# Control_HAT_v0_1B.net
KiCad netlist of a schematic drawn in EAGLE
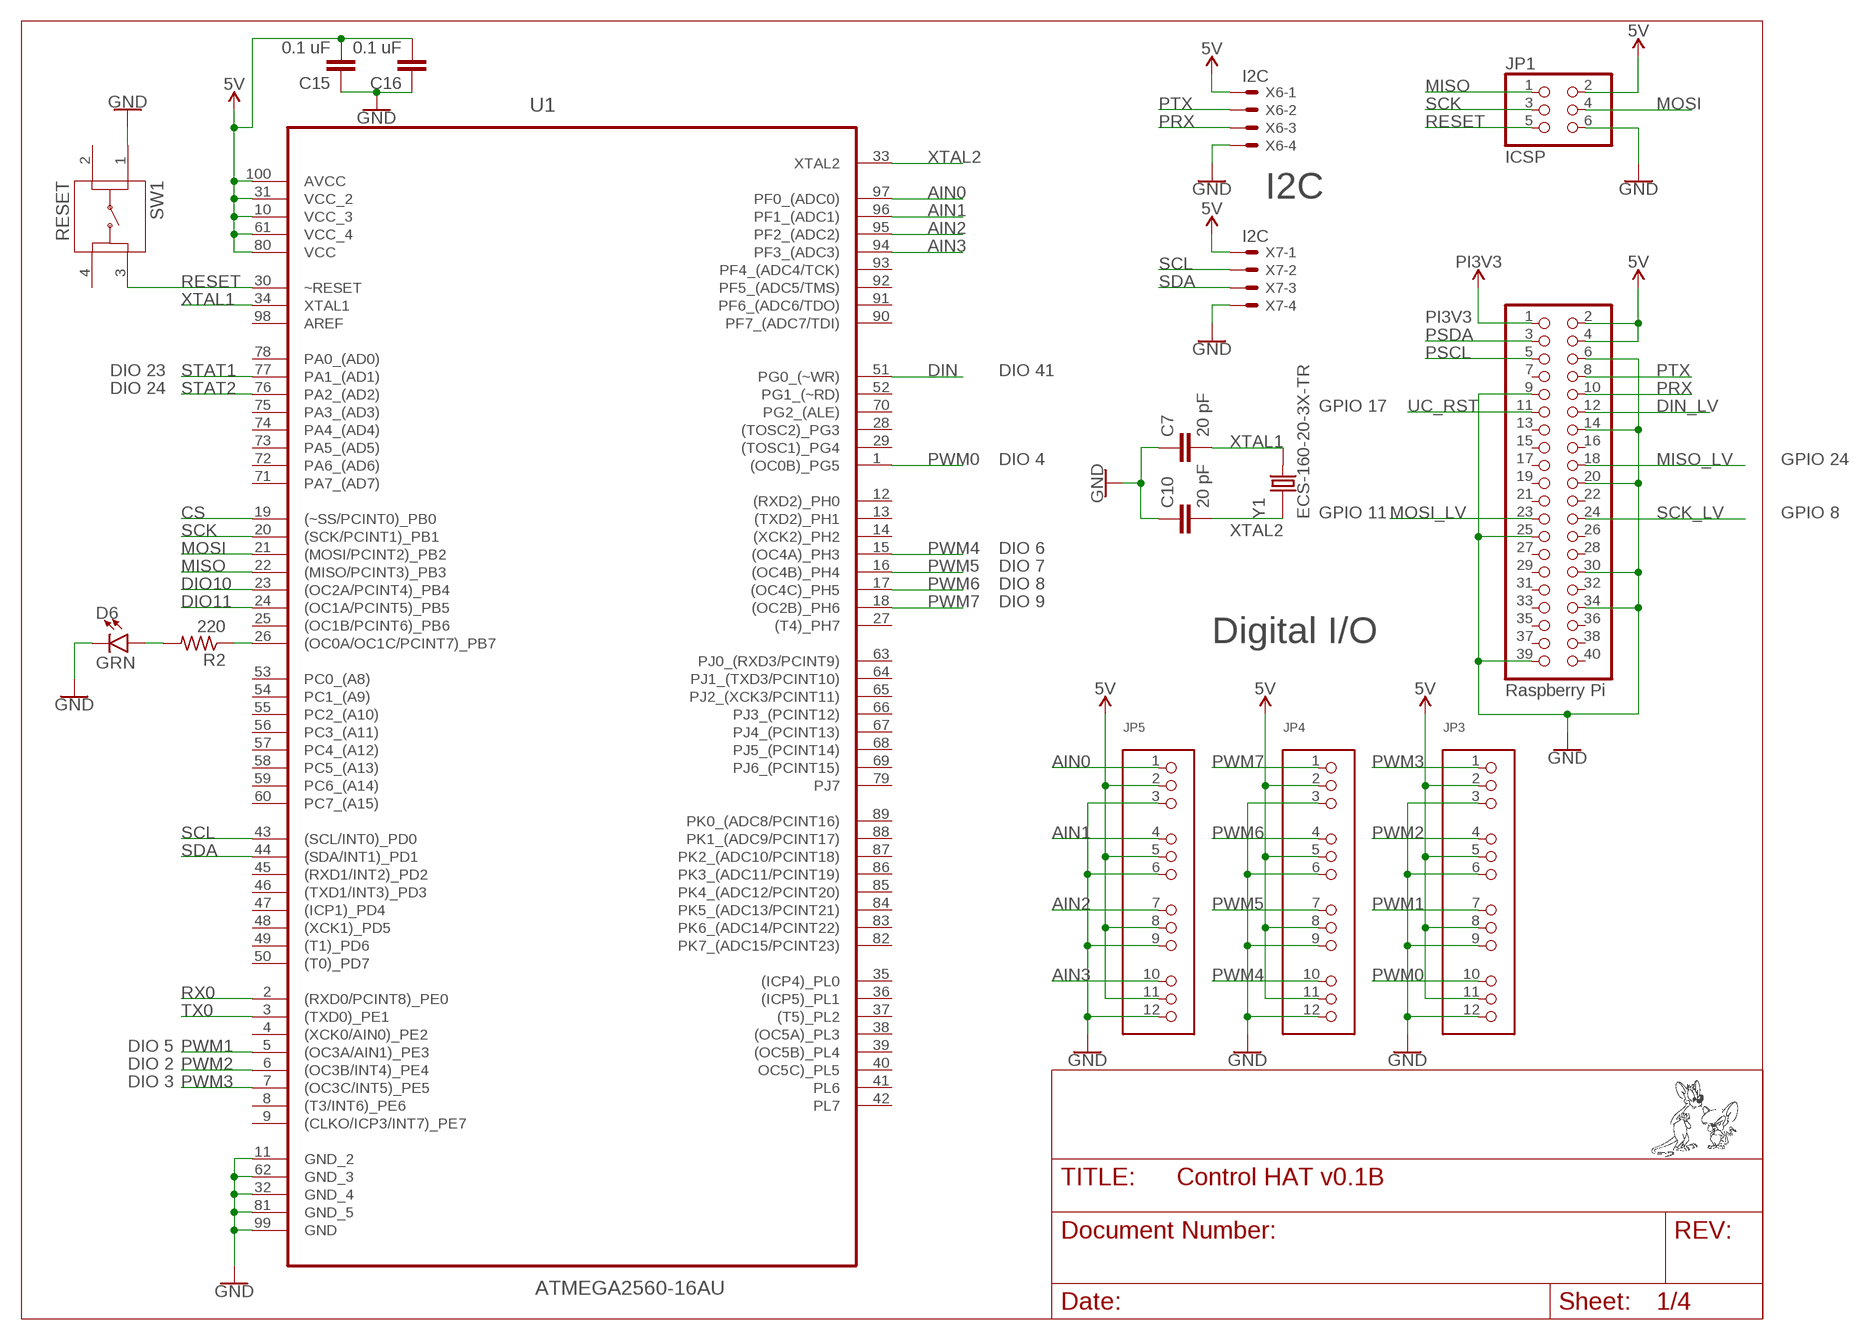
[diagram p0: schematic, sheet 1]
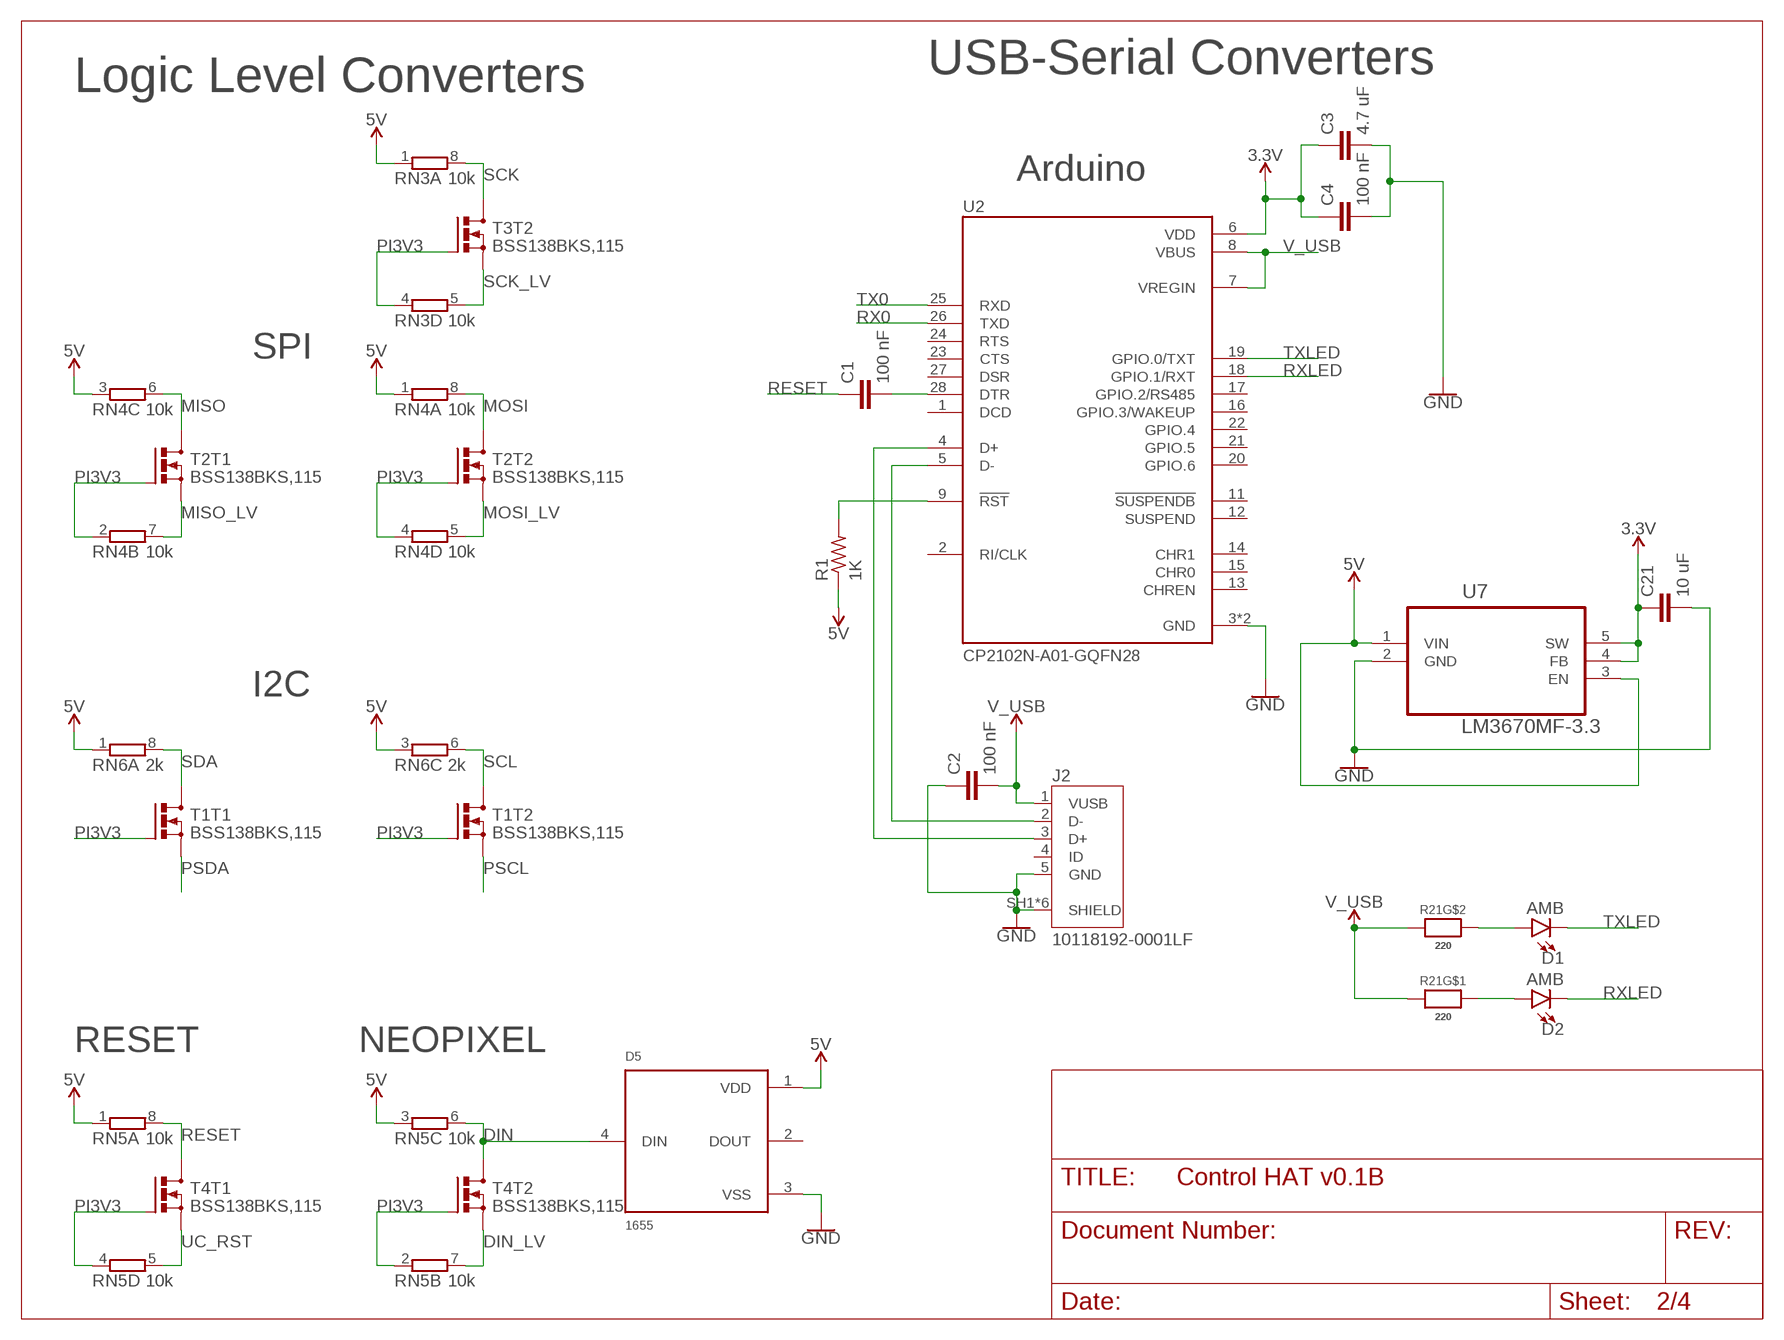
[diagram p1: schematic, sheet 2]
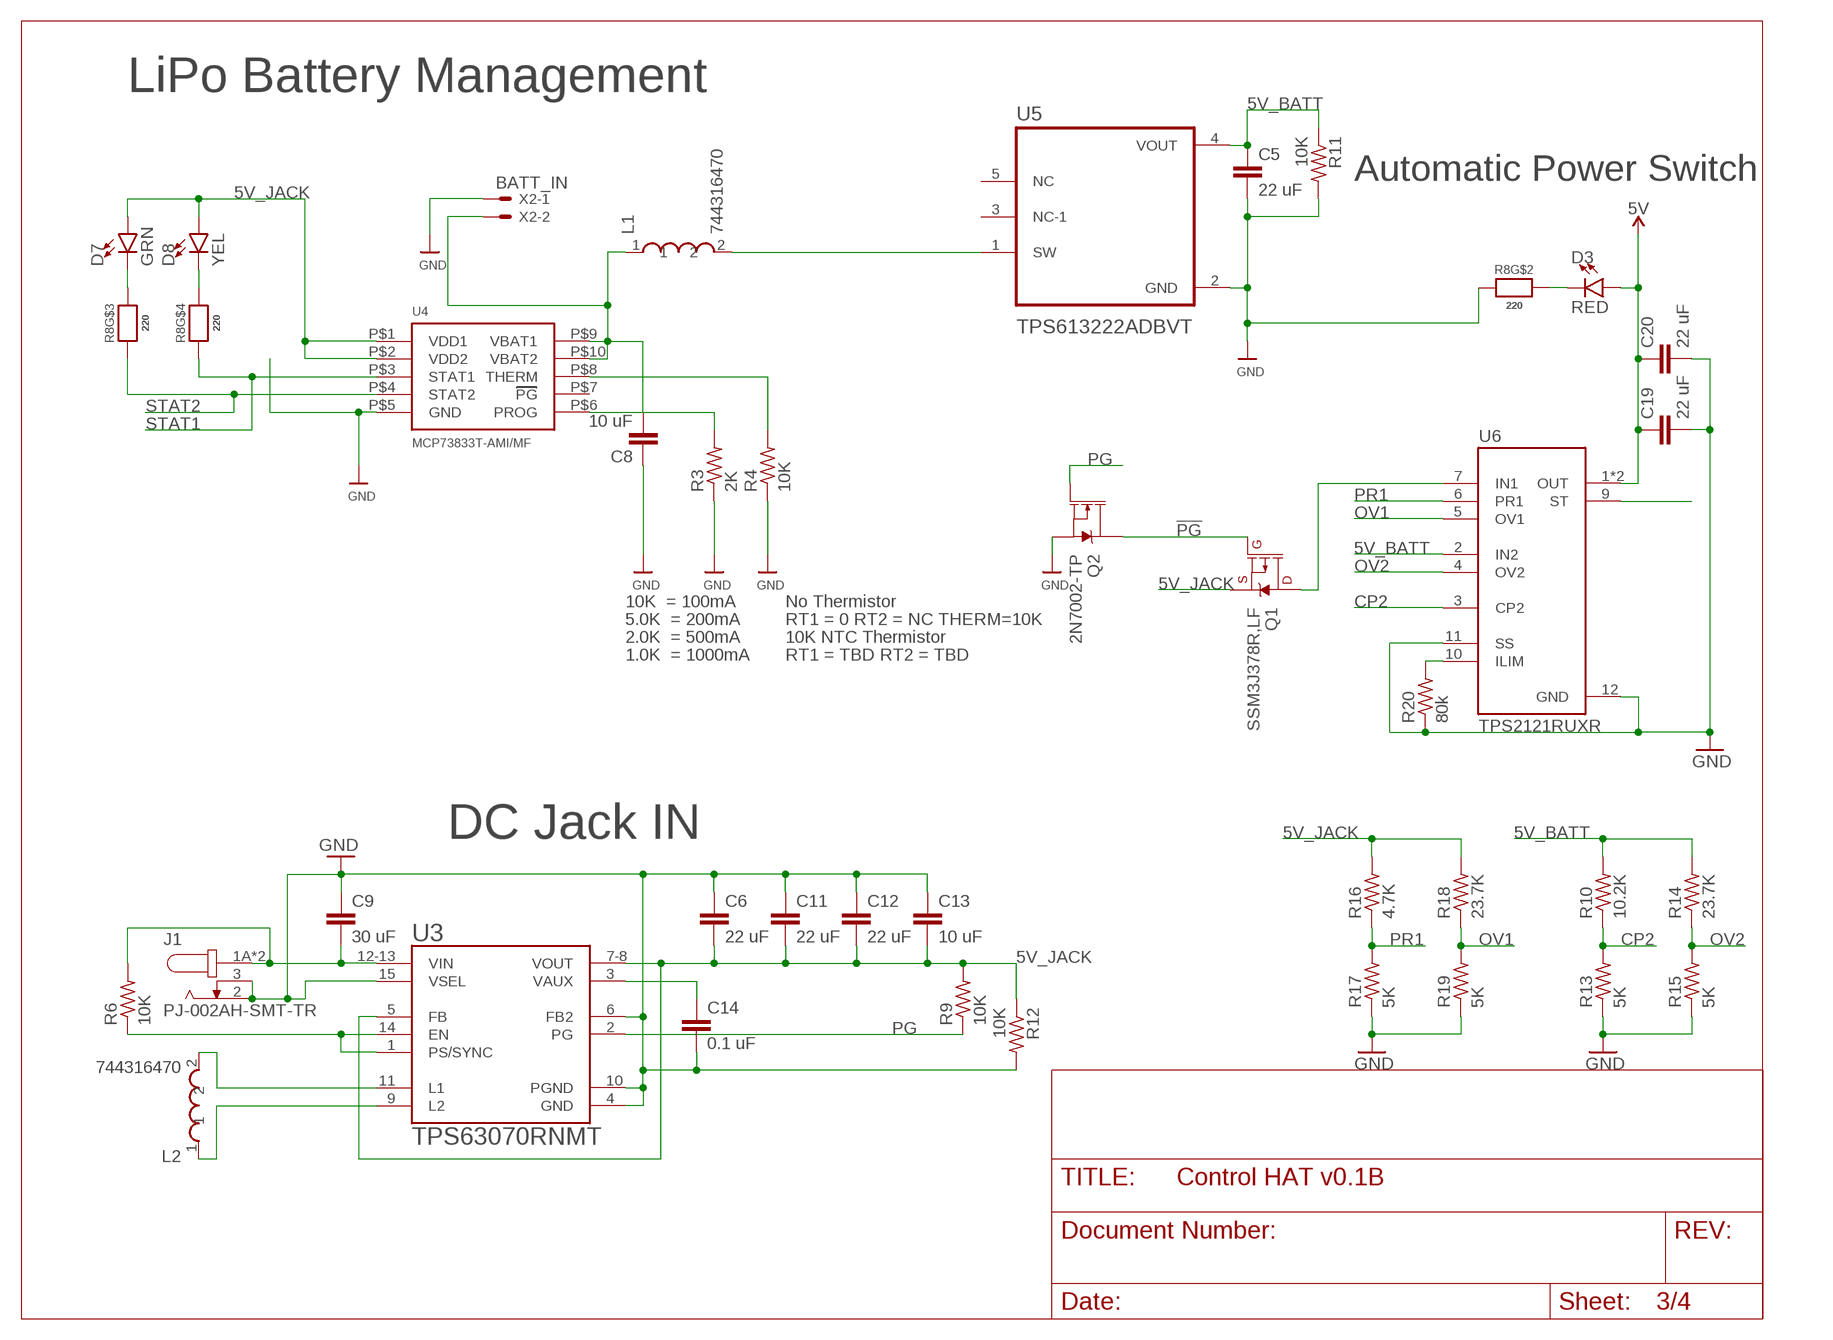
[diagram p2: schematic, sheet 3]
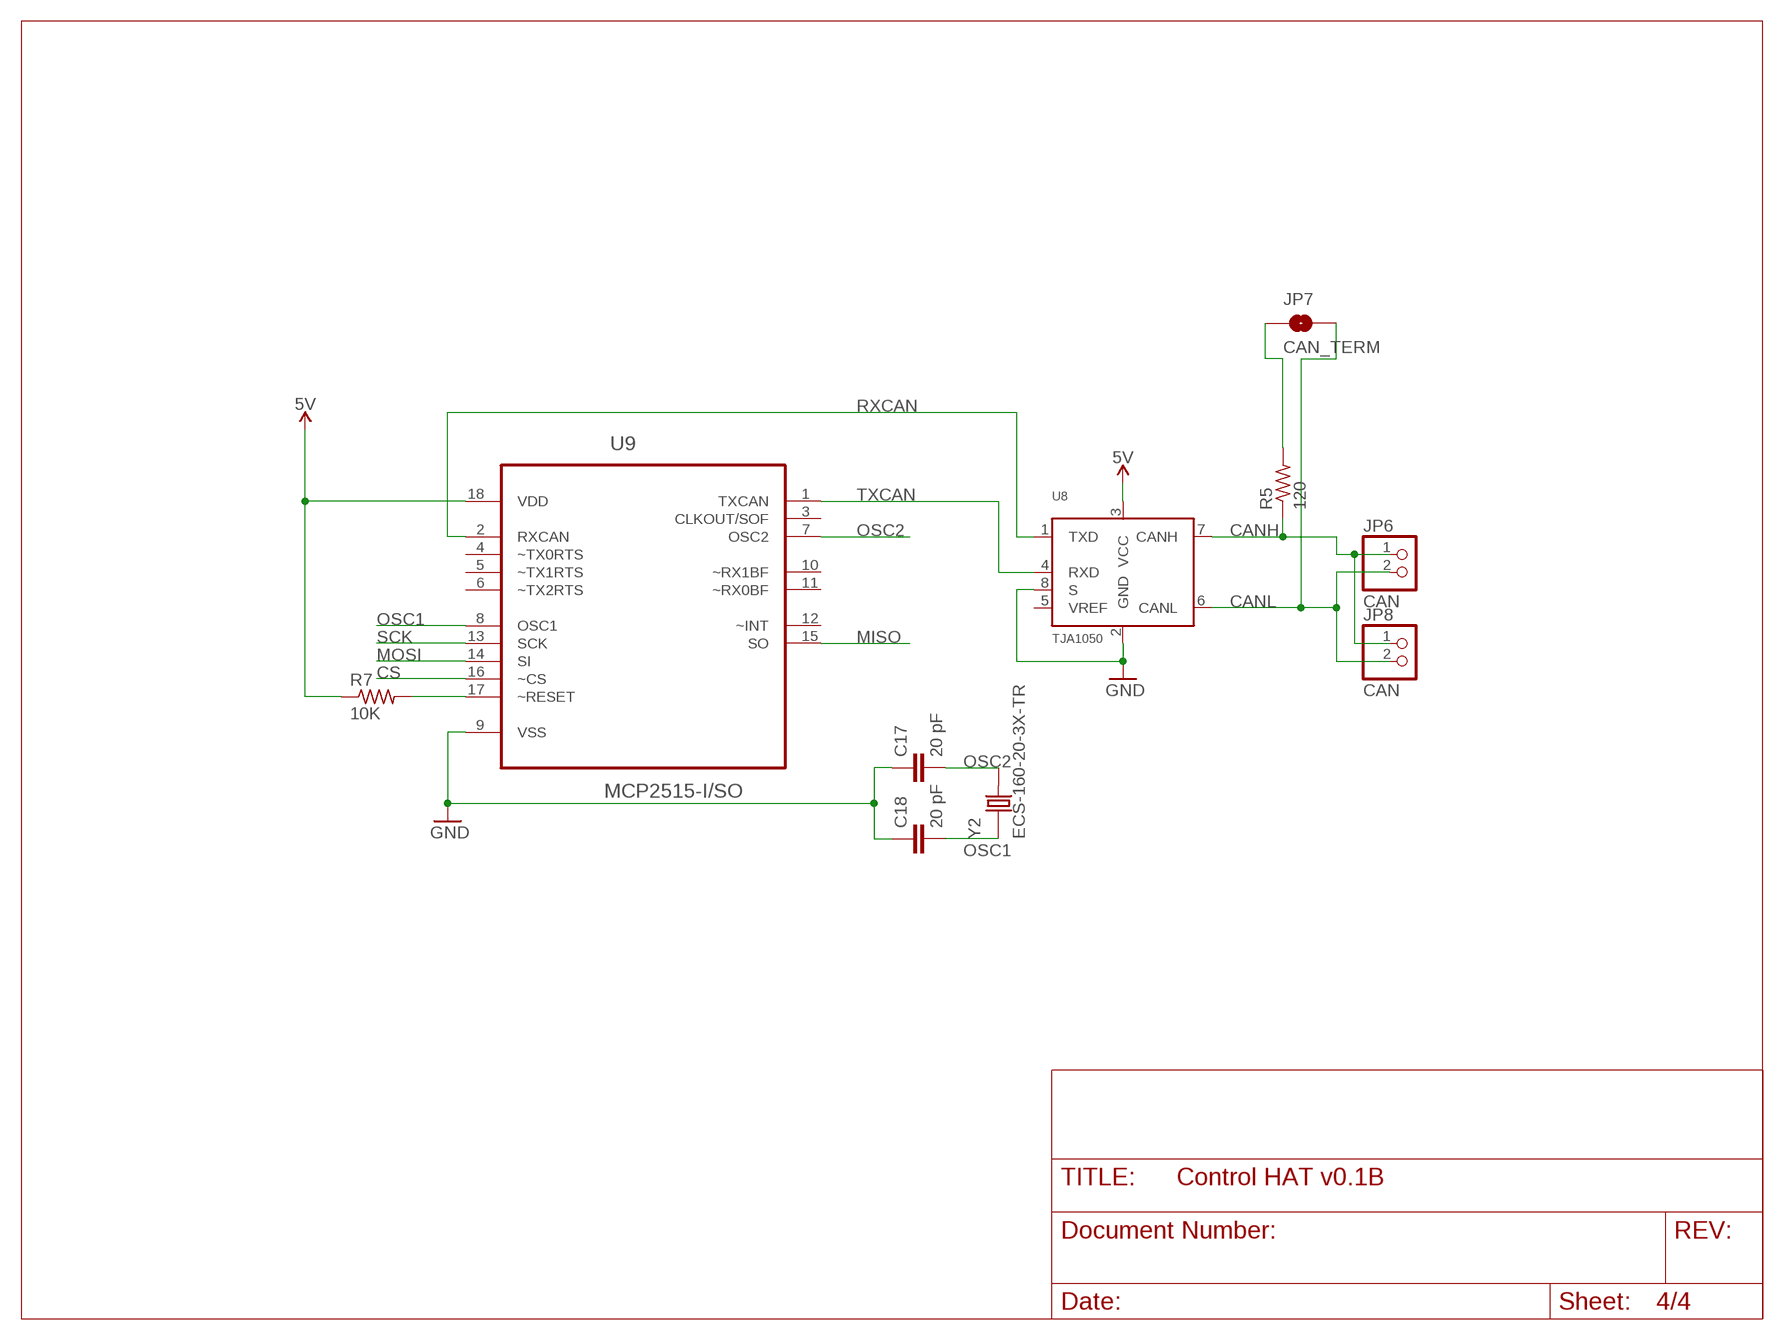
[diagram p3: schematic, sheet 4]

(export (version "E")
  (design (tool "Eeschema 10.0.6"))
  (components
    (comp (ref "C1")
      (value "100 nF")
      (footprint "eagle-import:C0603")
      (libsource (lib "eagle-import") (part "C-EUC0603"))
    )
    (comp (ref "C2")
      (value "100 nF")
      (footprint "eagle-import:C0603")
      (libsource (lib "eagle-import") (part "C-EUC0603"))
    )
    (comp (ref "C3")
      (value "4.7 uF")
      (footprint "eagle-import:C0603")
      (libsource (lib "eagle-import") (part "C-EUC0603"))
    )
    (comp (ref "C4")
      (value "100 nF")
      (footprint "eagle-import:C0603")
      (libsource (lib "eagle-import") (part "C-EUC0603"))
    )
    (comp (ref "C21")
      (value "10 uF")
      (footprint "eagle-import:C0603")
      (libsource (lib "eagle-import") (part "C-EUC0603"))
    )
    (comp (ref "D1")
      (value "AMB")
      (footprint "eagle-import:LED-0603")
      (libsource (lib "eagle-import") (part "LED0603"))
    )
    (comp (ref "D2")
      (value "AMB")
      (footprint "eagle-import:LED-0603")
      (libsource (lib "eagle-import") (part "LED0603"))
    )
    (comp (ref "D5")
      (value "1655")
      (footprint "eagle-import:FCI_1655")
      (fields (field (name "MF") "Adafruit Industries"))
      (libsource (lib "eagle-import") (part "1655"))
    )
    (comp (ref "J2")
      (value "10118192-0001LF")
      (footprint "eagle-import:AMPHENOL_10118192-0001LF")
      (fields (field (name "MF") "Amphenol ICC"))
      (libsource (lib "eagle-import") (part "10118192-0001LF"))
    )
    (comp (ref "R1")
      (value "1K")
      (footprint "eagle-import:R0603")
      (libsource (lib "eagle-import") (part "R-US_R0603"))
    )
    (comp (ref "R21")
      (value "220")
      (footprint "eagle-import:RESPACK_4X0603")
      (libsource (lib "eagle-import") (part "RESISTOR_4PACK"))
    )
    (comp (ref "RN3")
      (value "10k")
      (footprint "eagle-import:EXB28V")
      (libsource (lib "eagle-import") (part "4R-NEXB28V"))
    )
    (comp (ref "RN4")
      (value "10k")
      (footprint "eagle-import:EXB28V")
      (libsource (lib "eagle-import") (part "4R-NEXB28V"))
    )
    (comp (ref "RN5")
      (value "10k")
      (footprint "eagle-import:EXB28V")
      (libsource (lib "eagle-import") (part "4R-NEXB28V"))
    )
    (comp (ref "RN6")
      (value "2k")
      (footprint "eagle-import:EXB28V")
      (libsource (lib "eagle-import") (part "4R-NEXB28V"))
    )
    (comp (ref "T1")
      (value "BSS138BKS,115")
      (footprint "eagle-import:SOT363")
      (fields (field (name "MF") "Nexperia USA"))
      (libsource (lib "eagle-import") (part "BSS138BKS,115"))
    )
    (comp (ref "T2")
      (value "BSS138BKS,115")
      (footprint "eagle-import:SOT363")
      (fields (field (name "MF") "Nexperia USA"))
      (libsource (lib "eagle-import") (part "BSS138BKS,115"))
    )
    (comp (ref "T3")
      (value "BSS138BKS,115")
      (footprint "eagle-import:SOT363")
      (fields (field (name "MF") "Nexperia USA"))
      (libsource (lib "eagle-import") (part "BSS138BKS,115"))
    )
    (comp (ref "T4")
      (value "BSS138BKS,115")
      (footprint "eagle-import:SOT363")
      (fields (field (name "MF") "Nexperia USA"))
      (libsource (lib "eagle-import") (part "BSS138BKS,115"))
    )
    (comp (ref "U2")
      (value "CP2102N-A01-GQFN28")
      (footprint "eagle-import:QFN50P500X500X80-29N")
      (fields (field (name "MF") "Silicon Labs"))
      (libsource (lib "eagle-import") (part "CP2102N-A01-GQFN28"))
    )
    (comp (ref "U7")
      (value "LM3670MF-3.3")
      (footprint "eagle-import:SOT95P284X122-5N")
      (fields (field (name "MF") "Texas Instruments") (field (name "MP") "LM3670MF-3.3/NOPB"))
      (libsource (lib "eagle-import") (part "LM3670MF-3.3"))
    )
    (comp (ref "C17")
      (value "20 pF")
      (footprint "eagle-import:C0603")
      (libsource (lib "eagle-import") (part "C-EUC0603"))
    )
    (comp (ref "C18")
      (value "20 pF")
      (footprint "eagle-import:C0603")
      (libsource (lib "eagle-import") (part "C-EUC0603"))
    )
    (comp (ref "JP6")
      (value "CAN")
      (footprint "eagle-import:1X02")
      (libsource (lib "eagle-import") (part "PINHD-1X2"))
    )
    (comp (ref "JP7")
      (value "CAN_TERM")
      (footprint "eagle-import:SMT-JUMPER_2_NO_NO-SILK")
      (libsource (lib "eagle-import") (part "JUMPER-SMT_2_NO_NO-SILK"))
    )
    (comp (ref "JP8")
      (value "CAN")
      (footprint "eagle-import:1X02")
      (libsource (lib "eagle-import") (part "PINHD-1X2"))
    )
    (comp (ref "R5")
      (value "120")
      (footprint "eagle-import:R0603")
      (libsource (lib "eagle-import") (part "R-US_R0603"))
    )
    (comp (ref "R7")
      (value "10K")
      (footprint "eagle-import:R0603")
      (libsource (lib "eagle-import") (part "R-US_R0603"))
    )
    (comp (ref "U8")
      (value "TJA1050")
      (footprint "eagle-import:SOT96-1")
      (fields (field (name "DIGI-KEY_PART_NUMBER") "568-10292-1-ND") (field (name "MF") "NXP USA"))
      (libsource (lib "eagle-import") (part "TJA1050"))
    )
    (comp (ref "U9")
      (value "MCP2515-I/SO")
      (footprint "eagle-import:SOIC127P1034X264-18N")
      (fields (field (name "DIGI-KEY_PART_NUMBER") "MCP2515-I/SO-ND") (field (name "MF") "Microchip"))
      (libsource (lib "eagle-import") (part "MCP2515-I/SO"))
    )
    (comp (ref "Y2")
      (value "ECS-160-20-3X-TR")
      (footprint "eagle-import:XTAL_ECS-160-20-3X-TR")
      (fields (field (name "MF") "ECS Inc."))
      (libsource (lib "eagle-import") (part "ECS-160-20-3X-TR"))
    )
    (comp (ref "C5")
      (value "22 uF")
      (footprint "eagle-import:C0603")
      (libsource (lib "eagle-import") (part "C-EUC0603"))
    )
    (comp (ref "C6")
      (value "22 uF")
      (footprint "eagle-import:C0603")
      (libsource (lib "eagle-import") (part "C-EUC0603"))
    )
    (comp (ref "C8")
      (value "10 uF")
      (footprint "eagle-import:C0603")
      (libsource (lib "eagle-import") (part "C-EUC0603"))
    )
    (comp (ref "C9")
      (value "30 uF")
      (footprint "eagle-import:C0603")
      (libsource (lib "eagle-import") (part "C-EUC0603"))
    )
    (comp (ref "C11")
      (value "22 uF")
      (footprint "eagle-import:C0603")
      (libsource (lib "eagle-import") (part "C-EUC0603"))
    )
    (comp (ref "C12")
      (value "22 uF")
      (footprint "eagle-import:C0603")
      (libsource (lib "eagle-import") (part "C-EUC0603"))
    )
    (comp (ref "C13")
      (value "10 uF")
      (footprint "eagle-import:C0603")
      (libsource (lib "eagle-import") (part "C-EUC0603"))
    )
    (comp (ref "C14")
      (value "0.1 uF")
      (footprint "eagle-import:C0603")
      (libsource (lib "eagle-import") (part "C-EUC0603"))
    )
    (comp (ref "C19")
      (value "22 uF")
      (footprint "eagle-import:C0603")
      (libsource (lib "eagle-import") (part "C-EUC0603"))
    )
    (comp (ref "C20")
      (value "22 uF")
      (footprint "eagle-import:C0603")
      (libsource (lib "eagle-import") (part "C-EUC0603"))
    )
    (comp (ref "D3")
      (value "RED")
      (footprint "eagle-import:LED-0603")
      (libsource (lib "eagle-import") (part "LED0603"))
    )
    (comp (ref "D7")
      (value "GRN")
      (footprint "eagle-import:LED-0603")
      (libsource (lib "eagle-import") (part "LED0603"))
    )
    (comp (ref "D8")
      (value "YEL")
      (footprint "eagle-import:LED-0603")
      (libsource (lib "eagle-import") (part "LED0603"))
    )
    (comp (ref "J1")
      (value "PJ-002AH-SMT-TR")
      (footprint "eagle-import:CUI_PJ-002AH-SMT-TR")
      (fields (field (name "DIGI-KEY_PART_NUMBER") "CP-002AHPJCT-ND") (field (name "MF") "CUI Inc."))
      (libsource (lib "eagle-import") (part "PJ-002AH-SMT-TR"))
    )
    (comp (ref "L1")
      (value "744316470")
      (footprint "eagle-import:INDC2220X16")
      (fields (field (name "MF") "Wurth Electronics"))
      (libsource (lib "eagle-import") (part "744316470"))
    )
    (comp (ref "L2")
      (value "744316470")
      (footprint "eagle-import:INDC2220X16")
      (fields (field (name "MF") "Wurth Electronics"))
      (libsource (lib "eagle-import") (part "744316470"))
    )
    (comp (ref "Q1")
      (value "SSM3J378R,LF")
      (footprint "eagle-import:SOT23-3")
      (libsource (lib "eagle-import") (part "MOSFET_PCH-DMG2305UX-7"))
    )
    (comp (ref "Q2")
      (value "2N7002-TP")
      (footprint "eagle-import:SOT23-3")
      (libsource (lib "eagle-import") (part "MOSFET-NCH-AO3404A"))
    )
    (comp (ref "R3")
      (value "2K")
      (footprint "eagle-import:R0603")
      (libsource (lib "eagle-import") (part "R-US_R0603"))
    )
    (comp (ref "R4")
      (value "10K")
      (footprint "eagle-import:R0603")
      (libsource (lib "eagle-import") (part "R-US_R0603"))
    )
    (comp (ref "R6")
      (value "10K")
      (footprint "eagle-import:R0603")
      (libsource (lib "eagle-import") (part "R-US_R0603"))
    )
    (comp (ref "R8")
      (value "220")
      (footprint "eagle-import:RESPACK_4X0603")
      (libsource (lib "eagle-import") (part "RESISTOR_4PACK"))
    )
    (comp (ref "R9")
      (value "10K")
      (footprint "eagle-import:R0603")
      (libsource (lib "eagle-import") (part "R-US_R0603"))
    )
    (comp (ref "R10")
      (value "10.2K")
      (footprint "eagle-import:R0603")
      (libsource (lib "eagle-import") (part "R-US_R0603"))
    )
    (comp (ref "R11")
      (value "10K")
      (footprint "eagle-import:R0603")
      (libsource (lib "eagle-import") (part "R-US_R0603"))
    )
    (comp (ref "R12")
      (value "10K")
      (footprint "eagle-import:R0603")
      (libsource (lib "eagle-import") (part "R-US_R0603"))
    )
    (comp (ref "R13")
      (value "5K")
      (footprint "eagle-import:R0603")
      (libsource (lib "eagle-import") (part "R-US_R0603"))
    )
    (comp (ref "R14")
      (value "23.7K")
      (footprint "eagle-import:R0603")
      (libsource (lib "eagle-import") (part "R-US_R0603"))
    )
    (comp (ref "R15")
      (value "5K")
      (footprint "eagle-import:R0603")
      (libsource (lib "eagle-import") (part "R-US_R0603"))
    )
    (comp (ref "R16")
      (value "4.7K")
      (footprint "eagle-import:R0603")
      (libsource (lib "eagle-import") (part "R-US_R0603"))
    )
    (comp (ref "R17")
      (value "5K")
      (footprint "eagle-import:R0603")
      (libsource (lib "eagle-import") (part "R-US_R0603"))
    )
    (comp (ref "R18")
      (value "23.7K")
      (footprint "eagle-import:R0603")
      (libsource (lib "eagle-import") (part "R-US_R0603"))
    )
    (comp (ref "R19")
      (value "5K")
      (footprint "eagle-import:R0603")
      (libsource (lib "eagle-import") (part "R-US_R0603"))
    )
    (comp (ref "R20")
      (value "80k")
      (footprint "eagle-import:R0603")
      (libsource (lib "eagle-import") (part "R-US_R0603"))
    )
    (comp (ref "U3")
      (value "TPS63070RNMT")
      (footprint "eagle-import:QFN50P250X300X100-15N")
      (fields (field (name "MF") "Texas Instruments"))
      (libsource (lib "eagle-import") (part "TPS63070RNMT"))
    )
    (comp (ref "U4")
      (value "MCP73833T-AMI/MF")
      (footprint "eagle-import:DFN10_3X3MM")
      (libsource (lib "eagle-import") (part "MCP73833DFN"))
    )
    (comp (ref "U5")
      (value "TPS613222ADBVT")
      (footprint "eagle-import:SOT95P280X145-5N")
      (fields (field (name "MF") "Texas Instruments"))
      (libsource (lib "eagle-import") (part "TPS613222ADBVT"))
    )
    (comp (ref "U6")
      (value "TPS2121RUXR")
      (footprint "eagle-import:IC_TPS2121RUXR")
      (fields (field (name "MF") "Texas Instruments"))
      (libsource (lib "eagle-import") (part "TPS2121RUXR"))
    )
    (comp (ref "X2")
      (value "BATT_IN")
      (footprint "eagle-import:JST-XH-02-PACKAGE-LONG-PAD")
      (libsource (lib "eagle-import") (part "JST-XH-02-PIN-LONG-PAD"))
    )
    (comp (ref "C7")
      (value "20 pF")
      (footprint "eagle-import:C0603")
      (libsource (lib "eagle-import") (part "C-EUC0603"))
    )
    (comp (ref "C10")
      (value "20 pF")
      (footprint "eagle-import:C0603")
      (libsource (lib "eagle-import") (part "C-EUC0603"))
    )
    (comp (ref "C15")
      (value "0.1 uF")
      (footprint "eagle-import:C0603")
      (libsource (lib "eagle-import") (part "C-EUC0603"))
    )
    (comp (ref "C16")
      (value "0.1 uF")
      (footprint "eagle-import:C0603")
      (libsource (lib "eagle-import") (part "C-EUC0603"))
    )
    (comp (ref "D6")
      (value "GRN")
      (footprint "eagle-import:LED-0603")
      (libsource (lib "eagle-import") (part "LED0603"))
    )
    (comp (ref "JP1")
      (value "ICSP")
      (footprint "eagle-import:2X03")
      (libsource (lib "eagle-import") (part "PINHD-2X3"))
    )
    (comp (ref "JP2")
      (value "Raspberry Pi")
      (footprint "eagle-import:2X20")
      (libsource (lib "eagle-import") (part "PINHD-2X20"))
    )
    (comp (ref "JP3")
      (value "HEADER-3X04")
      (footprint "eagle-import:3X04")
      (libsource (lib "eagle-import") (part "HEADER-3X04"))
    )
    (comp (ref "JP4")
      (value "HEADER-3X04")
      (footprint "eagle-import:3X04")
      (libsource (lib "eagle-import") (part "HEADER-3X04"))
    )
    (comp (ref "JP5")
      (value "HEADER-3X04")
      (footprint "eagle-import:3X04")
      (libsource (lib "eagle-import") (part "HEADER-3X04"))
    )
    (comp (ref "R2")
      (value "220")
      (footprint "eagle-import:R0603")
      (libsource (lib "eagle-import") (part "R-US_R0603"))
    )
    (comp (ref "SW1")
      (value "RESET")
      (footprint "eagle-import:SW_1825910-6-4")
      (fields (field (name "COMMENT") "1825910-6") (field (name "MF") "TE Connectivity"))
      (libsource (lib "eagle-import") (part "1825910-6"))
    )
    (comp (ref "U1")
      (value "ATMEGA2560-16AU")
      (footprint "eagle-import:QFP50P1600X1600X120-100N")
      (fields (field (name "MF") "Microchip"))
      (libsource (lib "eagle-import") (part "ATMEGA2560-16AU"))
    )
    (comp (ref "X6")
      (value "I2C")
      (footprint "eagle-import:JST-XH-04-PACKAGE-LONG-PAD")
      (libsource (lib "eagle-import") (part "JST-XH-04-PIN-LONG-PAD"))
    )
    (comp (ref "X7")
      (value "I2C")
      (footprint "eagle-import:JST-XH-04-PACKAGE-LONG-PAD")
      (libsource (lib "eagle-import") (part "JST-XH-04-PIN-LONG-PAD"))
    )
    (comp (ref "Y1")
      (value "ECS-160-20-3X-TR")
      (footprint "eagle-import:XTAL_ECS-160-20-3X-TR")
      (fields (field (name "MF") "ECS Inc."))
      (libsource (lib "eagle-import") (part "ECS-160-20-3X-TR"))
    )
  )
  (nets
    (net (code "1") (name "3.3V") (class "Default")
      (node (ref "C21") (pin "1") (pinfunction "1_1") (pintype "passive"))
      (node (ref "C3") (pin "1") (pinfunction "1_1") (pintype "passive"))
      (node (ref "C4") (pin "1") (pinfunction "1_1") (pintype "passive"))
      (node (ref "U2") (pin "6") (pinfunction "VDD_6") (pintype "power_in"))
      (node (ref "U7") (pin "4") (pinfunction "FB_4") (pintype "passive"))
      (node (ref "U7") (pin "5") (pinfunction "SW_5") (pintype "output"))
    )
    (net (code "2") (name "5V") (class "Default")
      (node (ref "C15") (pin "2") (pinfunction "2_2") (pintype "passive"))
      (node (ref "C16") (pin "2") (pinfunction "2_2") (pintype "passive"))
      (node (ref "C19") (pin "1") (pinfunction "1_1") (pintype "passive"))
      (node (ref "C20") (pin "1") (pinfunction "1_1") (pintype "passive"))
      (node (ref "D3") (pin "A") (pinfunction "A_A") (pintype "passive"))
      (node (ref "D5") (pin "1") (pinfunction "VDD_1") (pintype "power_in"))
      (node (ref "JP1") (pin "2") (pinfunction "2_2") (pintype "passive"))
      (node (ref "JP2") (pin "2") (pinfunction "2_2") (pintype "passive"))
      (node (ref "JP2") (pin "4") (pinfunction "4_4") (pintype "passive"))
      (node (ref "JP3") (pin "11") (pinfunction "11_11") (pintype "passive"))
      (node (ref "JP3") (pin "2") (pinfunction "2_2") (pintype "passive"))
      (node (ref "JP3") (pin "5") (pinfunction "5_5") (pintype "passive"))
      (node (ref "JP3") (pin "8") (pinfunction "8_8") (pintype "passive"))
      (node (ref "JP4") (pin "11") (pinfunction "11_11") (pintype "passive"))
      (node (ref "JP4") (pin "2") (pinfunction "2_2") (pintype "passive"))
      (node (ref "JP4") (pin "5") (pinfunction "5_5") (pintype "passive"))
      (node (ref "JP4") (pin "8") (pinfunction "8_8") (pintype "passive"))
      (node (ref "JP5") (pin "11") (pinfunction "11_11") (pintype "passive"))
      (node (ref "JP5") (pin "2") (pinfunction "2_2") (pintype "passive"))
      (node (ref "JP5") (pin "5") (pinfunction "5_5") (pintype "passive"))
      (node (ref "JP5") (pin "8") (pinfunction "8_8") (pintype "passive"))
      (node (ref "R1") (pin "1") (pinfunction "1_1") (pintype "passive"))
      (node (ref "R7") (pin "1") (pinfunction "1_1") (pintype "passive"))
      (node (ref "RN3") (pin "1") (pinfunction "1_1") (pintype "passive"))
      (node (ref "RN4") (pin "1") (pinfunction "1_1") (pintype "passive"))
      (node (ref "RN4") (pin "3") (pinfunction "1_3") (pintype "passive"))
      (node (ref "RN5") (pin "1") (pinfunction "1_1") (pintype "passive"))
      (node (ref "RN5") (pin "3") (pinfunction "1_3") (pintype "passive"))
      (node (ref "RN6") (pin "1") (pinfunction "1_1") (pintype "passive"))
      (node (ref "RN6") (pin "3") (pinfunction "1_3") (pintype "passive"))
      (node (ref "U1") (pin "10") (pinfunction "VCC_3_10") (pintype "power_in"))
      (node (ref "U1") (pin "100") (pinfunction "AVCC_100") (pintype "power_in"))
      (node (ref "U1") (pin "31") (pinfunction "VCC_2_31") (pintype "power_in"))
      (node (ref "U1") (pin "61") (pinfunction "VCC_4_61") (pintype "power_in"))
      (node (ref "U1") (pin "80") (pinfunction "VCC_80") (pintype "power_in"))
      (node (ref "U6") (pin "1") (pinfunction "OUT_1") (pintype "output"))
      (node (ref "U6") (pin "8") (pinfunction "OUT_8") (pintype "output"))
      (node (ref "U7") (pin "1") (pinfunction "VIN_1") (pintype "input"))
      (node (ref "U7") (pin "3") (pinfunction "EN_3") (pintype "passive"))
      (node (ref "U8") (pin "3") (pinfunction "VCC_3") (pintype "bidirectional"))
      (node (ref "U9") (pin "18") (pinfunction "VDD_18") (pintype "power_in"))
      (node (ref "X6") (pin "1") (pinfunction "S_1") (pintype "passive"))
      (node (ref "X7") (pin "1") (pinfunction "S_1") (pintype "passive"))
    )
    (net (code "3") (name "5V_BATT") (class "Default")
      (node (ref "C5") (pin "1") (pinfunction "1_1") (pintype "passive"))
      (node (ref "R10") (pin "2") (pinfunction "2_2") (pintype "passive"))
      (node (ref "R11") (pin "1") (pinfunction "1_1") (pintype "passive"))
      (node (ref "R14") (pin "2") (pinfunction "2_2") (pintype "passive"))
      (node (ref "U5") (pin "4") (pinfunction "VOUT_4") (pintype "output"))
      (node (ref "U6") (pin "2") (pinfunction "IN2_2") (pintype "input"))
    )
    (net (code "4") (name "5V_JACK") (class "Default")
      (node (ref "C11") (pin "2") (pinfunction "2_2") (pintype "passive"))
      (node (ref "C12") (pin "2") (pinfunction "2_2") (pintype "passive"))
      (node (ref "C13") (pin "2") (pinfunction "2_2") (pintype "passive"))
      (node (ref "C6") (pin "2") (pinfunction "2_2") (pintype "passive"))
      (node (ref "D7") (pin "A") (pinfunction "A_A") (pintype "passive"))
      (node (ref "D8") (pin "A") (pinfunction "A_A") (pintype "passive"))
      (node (ref "Q1") (pin "2") (pinfunction "S_2") (pintype "bidirectional"))
      (node (ref "R12") (pin "1") (pinfunction "1_1") (pintype "passive"))
      (node (ref "R16") (pin "2") (pinfunction "2_2") (pintype "passive"))
      (node (ref "R18") (pin "2") (pinfunction "2_2") (pintype "passive"))
      (node (ref "R9") (pin "2") (pinfunction "2_2") (pintype "passive"))
      (node (ref "U3") (pin "5") (pinfunction "FB_5") (pintype "input"))
      (node (ref "U3") (pin "7-8") (pinfunction "VOUT_7-8") (pintype "output"))
      (node (ref "U4") (pin "P$1") (pinfunction "VDD1_P$1") (pintype "bidirectional"))
      (node (ref "U4") (pin "P$2") (pinfunction "VDD2_P$2") (pintype "bidirectional"))
    )
    (net (code "5") (name "AIN0") (class "Default")
      (node (ref "JP5") (pin "1") (pinfunction "1_1") (pintype "passive"))
      (node (ref "U1") (pin "97") (pinfunction "PF0_(ADC0)_97") (pintype "bidirectional"))
    )
    (net (code "6") (name "AIN1") (class "Default")
      (node (ref "JP5") (pin "4") (pinfunction "4_4") (pintype "passive"))
      (node (ref "U1") (pin "96") (pinfunction "PF1_(ADC1)_96") (pintype "bidirectional"))
    )
    (net (code "7") (name "AIN2") (class "Default")
      (node (ref "JP5") (pin "7") (pinfunction "7_7") (pintype "passive"))
      (node (ref "U1") (pin "95") (pinfunction "PF2_(ADC2)_95") (pintype "bidirectional"))
    )
    (net (code "8") (name "AIN3") (class "Default")
      (node (ref "JP5") (pin "10") (pinfunction "10_10") (pintype "passive"))
      (node (ref "U1") (pin "94") (pinfunction "PF3_(ADC3)_94") (pintype "bidirectional"))
    )
    (net (code "9") (name "CANH") (class "Default")
      (node (ref "JP6") (pin "1") (pinfunction "1_1") (pintype "passive"))
      (node (ref "JP8") (pin "1") (pinfunction "1_1") (pintype "passive"))
      (node (ref "R5") (pin "1") (pinfunction "1_1") (pintype "passive"))
      (node (ref "U8") (pin "7") (pinfunction "CANH_7") (pintype "bidirectional"))
    )
    (net (code "10") (name "CANL") (class "Default")
      (node (ref "JP6") (pin "2") (pinfunction "2_2") (pintype "passive"))
      (node (ref "JP7") (pin "2") (pinfunction "2_2") (pintype "passive"))
      (node (ref "JP8") (pin "2") (pinfunction "2_2") (pintype "passive"))
      (node (ref "U8") (pin "6") (pinfunction "CANL_6") (pintype "bidirectional"))
    )
    (net (code "11") (name "CP2") (class "Default")
      (node (ref "R10") (pin "1") (pinfunction "1_1") (pintype "passive"))
      (node (ref "R13") (pin "2") (pinfunction "2_2") (pintype "passive"))
      (node (ref "U6") (pin "3") (pinfunction "CP2_3") (pintype "input"))
    )
    (net (code "12") (name "CS") (class "Default")
      (node (ref "U1") (pin "19") (pinfunction "(~{SS/PCINT0})_PB0_19") (pintype "bidirectional"))
      (node (ref "U9") (pin "16") (pinfunction "~{CS}_16") (pintype "input"))
    )
    (net (code "13") (name "DIN") (class "Default")
      (node (ref "D5") (pin "4") (pinfunction "DIN_4") (pintype "input"))
      (node (ref "RN5") (pin "6") (pinfunction "2_6") (pintype "passive"))
      (node (ref "T4") (pin "3") (pinfunction "D_3") (pintype "passive"))
      (node (ref "U1") (pin "51") (pinfunction "PG0_(~{WR})_51") (pintype "bidirectional"))
    )
    (net (code "14") (name "DIN_LV") (class "Default")
      (node (ref "JP2") (pin "12") (pinfunction "12_12") (pintype "passive"))
      (node (ref "RN5") (pin "7") (pinfunction "2_7") (pintype "passive"))
      (node (ref "T4") (pin "4") (pinfunction "S_4") (pintype "passive"))
    )
    (net (code "15") (name "DIO10") (class "Default")
      (node (ref "U1") (pin "23") (pinfunction "(OC2A/PCINT4)_PB4_23") (pintype "bidirectional"))
    )
    (net (code "16") (name "DIO11") (class "Default")
      (node (ref "U1") (pin "24") (pinfunction "(OC1A/PCINT5)_PB5_24") (pintype "bidirectional"))
    )
    (net (code "17") (name "GND") (class "Default")
      (node (ref "C10") (pin "1") (pinfunction "1_1") (pintype "passive"))
      (node (ref "C11") (pin "1") (pinfunction "1_1") (pintype "passive"))
      (node (ref "C12") (pin "1") (pinfunction "1_1") (pintype "passive"))
      (node (ref "C13") (pin "1") (pinfunction "1_1") (pintype "passive"))
      (node (ref "C14") (pin "2") (pinfunction "2_2") (pintype "passive"))
      (node (ref "C15") (pin "1") (pinfunction "1_1") (pintype "passive"))
      (node (ref "C16") (pin "1") (pinfunction "1_1") (pintype "passive"))
      (node (ref "C17") (pin "1") (pinfunction "1_1") (pintype "passive"))
      (node (ref "C18") (pin "1") (pinfunction "1_1") (pintype "passive"))
      (node (ref "C19") (pin "2") (pinfunction "2_2") (pintype "passive"))
      (node (ref "C2") (pin "1") (pinfunction "1_1") (pintype "passive"))
      (node (ref "C20") (pin "2") (pinfunction "2_2") (pintype "passive"))
      (node (ref "C21") (pin "2") (pinfunction "2_2") (pintype "passive"))
      (node (ref "C3") (pin "2") (pinfunction "2_2") (pintype "passive"))
      (node (ref "C4") (pin "2") (pinfunction "2_2") (pintype "passive"))
      (node (ref "C5") (pin "2") (pinfunction "2_2") (pintype "passive"))
      (node (ref "C6") (pin "1") (pinfunction "1_1") (pintype "passive"))
      (node (ref "C7") (pin "1") (pinfunction "1_1") (pintype "passive"))
      (node (ref "C8") (pin "1") (pinfunction "1_1") (pintype "passive"))
      (node (ref "C9") (pin "1") (pinfunction "1_1") (pintype "passive"))
      (node (ref "D5") (pin "3") (pinfunction "VSS_3") (pintype "passive"))
      (node (ref "D6") (pin "C") (pinfunction "C_C") (pintype "passive"))
      (node (ref "J1") (pin "2") (pinfunction "2_2") (pintype "passive"))
      (node (ref "J1") (pin "3") (pinfunction "3_3") (pintype "passive"))
      (node (ref "J2") (pin "5") (pinfunction "GND_5") (pintype "passive"))
      (node (ref "J2") (pin "SH1") (pinfunction "SHIELD_SH1") (pintype "passive"))
      (node (ref "J2") (pin "SH2") (pinfunction "SHIELD_SH2") (pintype "passive"))
      (node (ref "J2") (pin "SH3") (pinfunction "SHIELD_SH3") (pintype "passive"))
      (node (ref "J2") (pin "SH4") (pinfunction "SHIELD_SH4") (pintype "passive"))
      (node (ref "J2") (pin "SH5") (pinfunction "SHIELD_SH5") (pintype "passive"))
      (node (ref "J2") (pin "SH6") (pinfunction "SHIELD_SH6") (pintype "passive"))
      (node (ref "JP1") (pin "6") (pinfunction "6_6") (pintype "passive"))
      (node (ref "JP2") (pin "14") (pinfunction "14_14") (pintype "passive"))
      (node (ref "JP2") (pin "20") (pinfunction "20_20") (pintype "passive"))
      (node (ref "JP2") (pin "25") (pinfunction "25_25") (pintype "passive"))
      (node (ref "JP2") (pin "30") (pinfunction "30_30") (pintype "passive"))
      (node (ref "JP2") (pin "34") (pinfunction "34_34") (pintype "passive"))
      (node (ref "JP2") (pin "39") (pinfunction "39_39") (pintype "passive"))
      (node (ref "JP2") (pin "6") (pinfunction "6_6") (pintype "passive"))
      (node (ref "JP2") (pin "9") (pinfunction "9_9") (pintype "passive"))
      (node (ref "JP3") (pin "12") (pinfunction "12_12") (pintype "passive"))
      (node (ref "JP3") (pin "3") (pinfunction "3_3") (pintype "passive"))
      (node (ref "JP3") (pin "6") (pinfunction "6_6") (pintype "passive"))
      (node (ref "JP3") (pin "9") (pinfunction "9_9") (pintype "passive"))
      (node (ref "JP4") (pin "12") (pinfunction "12_12") (pintype "passive"))
      (node (ref "JP4") (pin "3") (pinfunction "3_3") (pintype "passive"))
      (node (ref "JP4") (pin "6") (pinfunction "6_6") (pintype "passive"))
      (node (ref "JP4") (pin "9") (pinfunction "9_9") (pintype "passive"))
      (node (ref "JP5") (pin "12") (pinfunction "12_12") (pintype "passive"))
      (node (ref "JP5") (pin "3") (pinfunction "3_3") (pintype "passive"))
      (node (ref "JP5") (pin "6") (pinfunction "6_6") (pintype "passive"))
      (node (ref "JP5") (pin "9") (pinfunction "9_9") (pintype "passive"))
      (node (ref "Q2") (pin "2") (pinfunction "S_2") (pintype "bidirectional"))
      (node (ref "R11") (pin "2") (pinfunction "2_2") (pintype "passive"))
      (node (ref "R12") (pin "2") (pinfunction "2_2") (pintype "passive"))
      (node (ref "R13") (pin "1") (pinfunction "1_1") (pintype "passive"))
      (node (ref "R15") (pin "1") (pinfunction "1_1") (pintype "passive"))
      (node (ref "R17") (pin "1") (pinfunction "1_1") (pintype "passive"))
      (node (ref "R19") (pin "1") (pinfunction "1_1") (pintype "passive"))
      (node (ref "R20") (pin "1") (pinfunction "1_1") (pintype "passive"))
      (node (ref "R3") (pin "1") (pinfunction "1_1") (pintype "passive"))
      (node (ref "R4") (pin "1") (pinfunction "1_1") (pintype "passive"))
      (node (ref "R8") (pin "2") (pinfunction "1_2") (pintype "passive"))
      (node (ref "SW1") (pin "1") (pinfunction "1_1") (pintype "passive"))
      (node (ref "U1") (pin "11") (pinfunction "GND_2_11") (pintype "passive"))
      (node (ref "U1") (pin "32") (pinfunction "GND_4_32") (pintype "passive"))
      (node (ref "U1") (pin "62") (pinfunction "GND_3_62") (pintype "passive"))
      (node (ref "U1") (pin "81") (pinfunction "GND_5_81") (pintype "passive"))
      (node (ref "U1") (pin "99") (pinfunction "GND_99") (pintype "passive"))
      (node (ref "U2") (pin "29") (pinfunction "GND_29") (pintype "power_in"))
      (node (ref "U2") (pin "3") (pinfunction "GND_3") (pintype "power_in"))
      (node (ref "U3") (pin "10") (pinfunction "PGND_10") (pintype "power_in"))
      (node (ref "U3") (pin "15") (pinfunction "VSEL_15") (pintype "input"))
      (node (ref "U3") (pin "4") (pinfunction "GND_4") (pintype "power_in"))
      (node (ref "U3") (pin "6") (pinfunction "FB2_6") (pintype "output"))
      (node (ref "U4") (pin "P$5") (pinfunction "GND_P$5") (pintype "bidirectional"))
      (node (ref "U5") (pin "2") (pinfunction "GND_2") (pintype "power_in"))
      (node (ref "U6") (pin "11") (pinfunction "SS_11") (pintype "passive"))
      (node (ref "U6") (pin "12") (pinfunction "GND_12") (pintype "power_in"))
      (node (ref "U7") (pin "2") (pinfunction "GND_2") (pintype "passive"))
      (node (ref "U8") (pin "2") (pinfunction "GND_2") (pintype "bidirectional"))
      (node (ref "U8") (pin "8") (pinfunction "S_8") (pintype "power_in"))
      (node (ref "U9") (pin "9") (pinfunction "VSS_9") (pintype "power_in"))
      (node (ref "X2") (pin "1") (pinfunction "S_1") (pintype "passive"))
      (node (ref "X6") (pin "4") (pinfunction "S_4") (pintype "passive"))
      (node (ref "X7") (pin "4") (pinfunction "S_4") (pintype "passive"))
    )
    (net (code "18") (name "MISO") (class "Default")
      (node (ref "JP1") (pin "1") (pinfunction "1_1") (pintype "passive"))
      (node (ref "RN4") (pin "6") (pinfunction "2_6") (pintype "passive"))
      (node (ref "T2") (pin "6") (pinfunction "D_6") (pintype "passive"))
      (node (ref "U1") (pin "22") (pinfunction "(MISO/PCINT3)_PB3_22") (pintype "bidirectional"))
      (node (ref "U9") (pin "15") (pinfunction "SO_15") (pintype "output"))
    )
    (net (code "19") (name "MISO_LV") (class "Default")
      (node (ref "JP2") (pin "18") (pinfunction "18_18") (pintype "passive"))
      (node (ref "RN4") (pin "7") (pinfunction "2_7") (pintype "passive"))
      (node (ref "T2") (pin "1") (pinfunction "S_1") (pintype "passive"))
    )
    (net (code "20") (name "MOSI") (class "Default")
      (node (ref "JP1") (pin "4") (pinfunction "4_4") (pintype "passive"))
      (node (ref "RN4") (pin "8") (pinfunction "2_8") (pintype "passive"))
      (node (ref "T2") (pin "3") (pinfunction "D_3") (pintype "passive"))
      (node (ref "U1") (pin "21") (pinfunction "(MOSI/PCINT2)_PB2_21") (pintype "bidirectional"))
      (node (ref "U9") (pin "14") (pinfunction "SI_14") (pintype "input"))
    )
    (net (code "21") (name "MOSI_LV") (class "Default")
      (node (ref "JP2") (pin "23") (pinfunction "23_23") (pintype "passive"))
      (node (ref "RN4") (pin "5") (pinfunction "2_5") (pintype "passive"))
      (node (ref "T2") (pin "4") (pinfunction "S_4") (pintype "passive"))
    )
    (net (code "22") (name "Net-(D6-PadA)") (class "Default")
      (node (ref "D6") (pin "A") (pinfunction "A_A") (pintype "passive"))
      (node (ref "R2") (pin "2") (pinfunction "2_2") (pintype "passive"))
    )
    (net (code "23") (name "Net-(J2-D+)") (class "Default")
      (node (ref "J2") (pin "3") (pinfunction "D+_3") (pintype "passive"))
      (node (ref "U2") (pin "4") (pinfunction "D+_4") (pintype "bidirectional"))
    )
    (net (code "24") (name "Net-(J2-D-)") (class "Default")
      (node (ref "J2") (pin "2") (pinfunction "D-_2") (pintype "passive"))
      (node (ref "U2") (pin "5") (pinfunction "D-_5") (pintype "bidirectional"))
    )
    (net (code "25") (name "Net-(JP7-Pad1)") (class "Default")
      (node (ref "JP7") (pin "1") (pinfunction "1_1") (pintype "passive"))
      (node (ref "R5") (pin "2") (pinfunction "2_2") (pintype "passive"))
    )
    (net (code "26") (name "Net-(Q1-D)") (class "Default")
      (node (ref "Q1") (pin "3") (pinfunction "D_3") (pintype "bidirectional"))
      (node (ref "U6") (pin "7") (pinfunction "IN1_7") (pintype "input"))
    )
    (net (code "27") (name "Net-(R8B-2)") (class "Default")
      (node (ref "D3") (pin "C") (pinfunction "C_C") (pintype "passive"))
      (node (ref "R8") (pin "7") (pinfunction "2_7") (pintype "passive"))
    )
    (net (code "28") (name "Net-(R8C-2)") (class "Default")
      (node (ref "D7") (pin "C") (pinfunction "C_C") (pintype "passive"))
      (node (ref "R8") (pin "6") (pinfunction "2_6") (pintype "passive"))
    )
    (net (code "29") (name "Net-(R8D-2)") (class "Default")
      (node (ref "D8") (pin "C") (pinfunction "C_C") (pintype "passive"))
      (node (ref "R8") (pin "5") (pinfunction "2_5") (pintype "passive"))
    )
    (net (code "30") (name "Net-(R21A-2)") (class "Default")
      (node (ref "D2") (pin "A") (pinfunction "A_A") (pintype "passive"))
      (node (ref "R21") (pin "8") (pinfunction "2_8") (pintype "passive"))
    )
    (net (code "31") (name "Net-(R21B-2)") (class "Default")
      (node (ref "D1") (pin "A") (pinfunction "A_A") (pintype "passive"))
      (node (ref "R21") (pin "7") (pinfunction "2_7") (pintype "passive"))
    )
    (net (code "32") (name "Net-(U1-(OC0A{slash}OC1C{slash}PCINT7)_PB7)") (class "Default")
      (node (ref "R2") (pin "1") (pinfunction "1_1") (pintype "passive"))
      (node (ref "U1") (pin "26") (pinfunction "(OC0A/OC1C/PCINT7)_PB7_26") (pintype "bidirectional"))
    )
    (net (code "33") (name "Net-(U2-DTR)") (class "Default")
      (node (ref "C1") (pin "2") (pinfunction "2_2") (pintype "passive"))
      (node (ref "U2") (pin "28") (pinfunction "DTR_28") (pintype "output"))
    )
    (net (code "34") (name "Net-(U2-~{RST})") (class "Default")
      (node (ref "R1") (pin "2") (pinfunction "2_2") (pintype "passive"))
      (node (ref "U2") (pin "9") (pinfunction "~{RST}_9") (pintype "input"))
    )
    (net (code "35") (name "Net-(U3-EN)") (class "Default")
      (node (ref "R6") (pin "1") (pinfunction "1_1") (pintype "passive"))
      (node (ref "U3") (pin "1") (pinfunction "PS/SYNC_1") (pintype "input"))
      (node (ref "U3") (pin "14") (pinfunction "EN_14") (pintype "input"))
    )
    (net (code "36") (name "Net-(U3-L1)") (class "Default")
      (node (ref "L2") (pin "2") (pinfunction "2_2") (pintype "passive"))
      (node (ref "U3") (pin "11") (pinfunction "L1_11") (pintype "input"))
    )
    (net (code "37") (name "Net-(U3-L2)") (class "Default")
      (node (ref "L2") (pin "1") (pinfunction "1_1") (pintype "passive"))
      (node (ref "U3") (pin "9") (pinfunction "L2_9") (pintype "input"))
    )
    (net (code "38") (name "Net-(U3-VAUX)") (class "Default")
      (node (ref "C14") (pin "1") (pinfunction "1_1") (pintype "passive"))
      (node (ref "U3") (pin "3") (pinfunction "VAUX_3") (pintype "output"))
    )
    (net (code "39") (name "Net-(U3-VIN)") (class "Default")
      (node (ref "C9") (pin "2") (pinfunction "2_2") (pintype "passive"))
      (node (ref "J1") (pin "1A") (pinfunction "1_1A") (pintype "passive"))
      (node (ref "J1") (pin "1B") (pinfunction "1_1B") (pintype "passive"))
      (node (ref "R6") (pin "2") (pinfunction "2_2") (pintype "passive"))
      (node (ref "U3") (pin "12-13") (pinfunction "VIN_12-13") (pintype "input"))
    )
    (net (code "40") (name "Net-(U4-PROG)") (class "Default")
      (node (ref "R3") (pin "2") (pinfunction "2_2") (pintype "passive"))
      (node (ref "U4") (pin "P$6") (pinfunction "PROG_P$6") (pintype "bidirectional"))
    )
    (net (code "41") (name "Net-(U4-THERM)") (class "Default")
      (node (ref "R4") (pin "2") (pinfunction "2_2") (pintype "passive"))
      (node (ref "U4") (pin "P$8") (pinfunction "THERM_P$8") (pintype "bidirectional"))
    )
    (net (code "42") (name "Net-(U4-VBAT1)") (class "Default")
      (node (ref "C8") (pin "2") (pinfunction "2_2") (pintype "passive"))
      (node (ref "L1") (pin "1") (pinfunction "1_1") (pintype "passive"))
      (node (ref "U4") (pin "P$10") (pinfunction "VBAT2_P$10") (pintype "bidirectional"))
      (node (ref "U4") (pin "P$9") (pinfunction "VBAT1_P$9") (pintype "bidirectional"))
      (node (ref "X2") (pin "2") (pinfunction "S_2") (pintype "passive"))
    )
    (net (code "43") (name "Net-(U5-SW)") (class "Default")
      (node (ref "L1") (pin "2") (pinfunction "2_2") (pintype "passive"))
      (node (ref "U5") (pin "1") (pinfunction "SW_1") (pintype "bidirectional"))
    )
    (net (code "44") (name "Net-(U6-ILIM)") (class "Default")
      (node (ref "R20") (pin "2") (pinfunction "2_2") (pintype "passive"))
      (node (ref "U6") (pin "10") (pinfunction "ILIM_10") (pintype "passive"))
    )
    (net (code "45") (name "Net-(U9-~{RESET})") (class "Default")
      (node (ref "R7") (pin "2") (pinfunction "2_2") (pintype "passive"))
      (node (ref "U9") (pin "17") (pinfunction "~{RESET}_17") (pintype "input"))
    )
    (net (code "46") (name "OSC1") (class "Default")
      (node (ref "C18") (pin "2") (pinfunction "2_2") (pintype "passive"))
      (node (ref "U9") (pin "8") (pinfunction "OSC1_8") (pintype "input"))
      (node (ref "Y2") (pin "1") (pinfunction "1_1") (pintype "passive"))
    )
    (net (code "47") (name "OSC2") (class "Default")
      (node (ref "C17") (pin "2") (pinfunction "2_2") (pintype "passive"))
      (node (ref "U9") (pin "7") (pinfunction "OSC2_7") (pintype "output"))
      (node (ref "Y2") (pin "2") (pinfunction "2_2") (pintype "passive"))
    )
    (net (code "48") (name "OV1") (class "Default")
      (node (ref "R18") (pin "1") (pinfunction "1_1") (pintype "passive"))
      (node (ref "R19") (pin "2") (pinfunction "2_2") (pintype "passive"))
      (node (ref "U6") (pin "5") (pinfunction "OV1_5") (pintype "input"))
    )
    (net (code "49") (name "OV2") (class "Default")
      (node (ref "R14") (pin "1") (pinfunction "1_1") (pintype "passive"))
      (node (ref "R15") (pin "2") (pinfunction "2_2") (pintype "passive"))
      (node (ref "U6") (pin "4") (pinfunction "OV2_4") (pintype "input"))
    )
    (net (code "50") (name "PG") (class "Default")
      (node (ref "Q2") (pin "1") (pinfunction "G_1") (pintype "bidirectional"))
      (node (ref "R9") (pin "1") (pinfunction "1_1") (pintype "passive"))
      (node (ref "U3") (pin "2") (pinfunction "PG_2") (pintype "output"))
    )
    (net (code "51") (name "PI3V3") (class "Default")
      (node (ref "JP2") (pin "1") (pinfunction "1_1") (pintype "passive"))
      (node (ref "RN3") (pin "4") (pinfunction "1_4") (pintype "passive"))
      (node (ref "RN4") (pin "2") (pinfunction "1_2") (pintype "passive"))
      (node (ref "RN4") (pin "4") (pinfunction "1_4") (pintype "passive"))
      (node (ref "RN5") (pin "2") (pinfunction "1_2") (pintype "passive"))
      (node (ref "RN5") (pin "4") (pinfunction "1_4") (pintype "passive"))
      (node (ref "T1") (pin "2") (pinfunction "G_2") (pintype "passive"))
      (node (ref "T1") (pin "5") (pinfunction "G_5") (pintype "passive"))
      (node (ref "T2") (pin "2") (pinfunction "G_2") (pintype "passive"))
      (node (ref "T2") (pin "5") (pinfunction "G_5") (pintype "passive"))
      (node (ref "T3") (pin "5") (pinfunction "G_5") (pintype "passive"))
      (node (ref "T4") (pin "2") (pinfunction "G_2") (pintype "passive"))
      (node (ref "T4") (pin "5") (pinfunction "G_5") (pintype "passive"))
    )
    (net (code "52") (name "PR1") (class "Default")
      (node (ref "R16") (pin "1") (pinfunction "1_1") (pintype "passive"))
      (node (ref "R17") (pin "2") (pinfunction "2_2") (pintype "passive"))
      (node (ref "U6") (pin "6") (pinfunction "PR1_6") (pintype "input"))
    )
    (net (code "53") (name "PRX") (class "Default")
      (node (ref "JP2") (pin "10") (pinfunction "10_10") (pintype "passive"))
      (node (ref "X6") (pin "3") (pinfunction "S_3") (pintype "passive"))
    )
    (net (code "54") (name "PSCL") (class "Default")
      (node (ref "JP2") (pin "5") (pinfunction "5_5") (pintype "passive"))
      (node (ref "T1") (pin "4") (pinfunction "S_4") (pintype "passive"))
    )
    (net (code "55") (name "PSDA") (class "Default")
      (node (ref "JP2") (pin "3") (pinfunction "3_3") (pintype "passive"))
      (node (ref "T1") (pin "1") (pinfunction "S_1") (pintype "passive"))
    )
    (net (code "56") (name "PTX") (class "Default")
      (node (ref "JP2") (pin "8") (pinfunction "8_8") (pintype "passive"))
      (node (ref "X6") (pin "2") (pinfunction "S_2") (pintype "passive"))
    )
    (net (code "57") (name "PWM0") (class "Default")
      (node (ref "JP3") (pin "10") (pinfunction "10_10") (pintype "passive"))
      (node (ref "U1") (pin "1") (pinfunction "(OC0B)_PG5_1") (pintype "bidirectional"))
    )
    (net (code "58") (name "PWM1") (class "Default")
      (node (ref "JP3") (pin "7") (pinfunction "7_7") (pintype "passive"))
      (node (ref "U1") (pin "5") (pinfunction "(OC3A/AIN1)_PE3_5") (pintype "bidirectional"))
    )
    (net (code "59") (name "PWM2") (class "Default")
      (node (ref "JP3") (pin "4") (pinfunction "4_4") (pintype "passive"))
      (node (ref "U1") (pin "6") (pinfunction "(OC3B/INT4)_PE4_6") (pintype "bidirectional"))
    )
    (net (code "60") (name "PWM3") (class "Default")
      (node (ref "JP3") (pin "1") (pinfunction "1_1") (pintype "passive"))
      (node (ref "U1") (pin "7") (pinfunction "(OC3C/INT5)_PE5_7") (pintype "bidirectional"))
    )
    (net (code "61") (name "PWM4") (class "Default")
      (node (ref "JP4") (pin "10") (pinfunction "10_10") (pintype "passive"))
      (node (ref "U1") (pin "15") (pinfunction "(OC4A)_PH3_15") (pintype "bidirectional"))
    )
    (net (code "62") (name "PWM5") (class "Default")
      (node (ref "JP4") (pin "7") (pinfunction "7_7") (pintype "passive"))
      (node (ref "U1") (pin "16") (pinfunction "(OC4B)_PH4_16") (pintype "bidirectional"))
    )
    (net (code "63") (name "PWM6") (class "Default")
      (node (ref "JP4") (pin "4") (pinfunction "4_4") (pintype "passive"))
      (node (ref "U1") (pin "17") (pinfunction "(OC4C)_PH5_17") (pintype "bidirectional"))
    )
    (net (code "64") (name "PWM7") (class "Default")
      (node (ref "JP4") (pin "1") (pinfunction "1_1") (pintype "passive"))
      (node (ref "U1") (pin "18") (pinfunction "(OC2B)_PH6_18") (pintype "bidirectional"))
    )
    (net (code "65") (name "RESET") (class "Default")
      (node (ref "C1") (pin "1") (pinfunction "1_1") (pintype "passive"))
      (node (ref "JP1") (pin "5") (pinfunction "5_5") (pintype "passive"))
      (node (ref "RN5") (pin "8") (pinfunction "2_8") (pintype "passive"))
      (node (ref "SW1") (pin "3") (pinfunction "3_3") (pintype "passive"))
      (node (ref "T4") (pin "6") (pinfunction "D_6") (pintype "passive"))
      (node (ref "U1") (pin "30") (pinfunction "~{RESET}_30") (pintype "input"))
    )
    (net (code "66") (name "RX0") (class "Default")
      (node (ref "U1") (pin "2") (pinfunction "(RXD0/PCINT8)_PE0_2") (pintype "bidirectional"))
      (node (ref "U2") (pin "26") (pinfunction "TXD_26") (pintype "output"))
    )
    (net (code "67") (name "RXCAN") (class "Default")
      (node (ref "U8") (pin "1") (pinfunction "TXD_1") (pintype "output"))
      (node (ref "U9") (pin "2") (pinfunction "RXCAN_2") (pintype "input"))
    )
    (net (code "68") (name "RXLED") (class "Default")
      (node (ref "D2") (pin "C") (pinfunction "C_C") (pintype "passive"))
      (node (ref "U2") (pin "18") (pinfunction "GPIO.1/RXT_18") (pintype "bidirectional"))
    )
    (net (code "69") (name "SCK") (class "Default")
      (node (ref "JP1") (pin "3") (pinfunction "3_3") (pintype "passive"))
      (node (ref "RN3") (pin "8") (pinfunction "2_8") (pintype "passive"))
      (node (ref "T3") (pin "3") (pinfunction "D_3") (pintype "passive"))
      (node (ref "U1") (pin "20") (pinfunction "(SCK/PCINT1)_PB1_20") (pintype "bidirectional"))
      (node (ref "U9") (pin "13") (pinfunction "SCK_13") (pintype "input"))
    )
    (net (code "70") (name "SCK_LV") (class "Default")
      (node (ref "JP2") (pin "24") (pinfunction "24_24") (pintype "passive"))
      (node (ref "RN3") (pin "5") (pinfunction "2_5") (pintype "passive"))
      (node (ref "T3") (pin "4") (pinfunction "S_4") (pintype "passive"))
    )
    (net (code "71") (name "SCL") (class "Default")
      (node (ref "RN6") (pin "6") (pinfunction "2_6") (pintype "passive"))
      (node (ref "T1") (pin "3") (pinfunction "D_3") (pintype "passive"))
      (node (ref "U1") (pin "43") (pinfunction "(SCL/INT0)_PD0_43") (pintype "bidirectional"))
      (node (ref "X7") (pin "2") (pinfunction "S_2") (pintype "passive"))
    )
    (net (code "72") (name "SDA") (class "Default")
      (node (ref "RN6") (pin "8") (pinfunction "2_8") (pintype "passive"))
      (node (ref "T1") (pin "6") (pinfunction "D_6") (pintype "passive"))
      (node (ref "U1") (pin "44") (pinfunction "(SDA/INT1)_PD1_44") (pintype "bidirectional"))
      (node (ref "X7") (pin "3") (pinfunction "S_3") (pintype "passive"))
    )
    (net (code "73") (name "STAT1") (class "Default")
      (node (ref "R8") (pin "4") (pinfunction "1_4") (pintype "passive"))
      (node (ref "U1") (pin "77") (pinfunction "PA1_(AD1)_77") (pintype "bidirectional"))
      (node (ref "U4") (pin "P$3") (pinfunction "STAT1_P$3") (pintype "bidirectional"))
    )
    (net (code "74") (name "STAT2") (class "Default")
      (node (ref "R8") (pin "3") (pinfunction "1_3") (pintype "passive"))
      (node (ref "U1") (pin "76") (pinfunction "PA2_(AD2)_76") (pintype "bidirectional"))
      (node (ref "U4") (pin "P$4") (pinfunction "STAT2_P$4") (pintype "bidirectional"))
    )
    (net (code "75") (name "TX0") (class "Default")
      (node (ref "U1") (pin "3") (pinfunction "(TXD0)_PE1_3") (pintype "bidirectional"))
      (node (ref "U2") (pin "25") (pinfunction "RXD_25") (pintype "input"))
    )
    (net (code "76") (name "TXCAN") (class "Default")
      (node (ref "U8") (pin "4") (pinfunction "RXD_4") (pintype "bidirectional"))
      (node (ref "U9") (pin "1") (pinfunction "TXCAN_1") (pintype "output"))
    )
    (net (code "77") (name "TXLED") (class "Default")
      (node (ref "D1") (pin "C") (pinfunction "C_C") (pintype "passive"))
      (node (ref "U2") (pin "19") (pinfunction "GPIO.0/TXT_19") (pintype "bidirectional"))
    )
    (net (code "78") (name "UC_RST") (class "Default")
      (node (ref "JP2") (pin "11") (pinfunction "11_11") (pintype "passive"))
      (node (ref "RN5") (pin "5") (pinfunction "2_5") (pintype "passive"))
      (node (ref "T4") (pin "1") (pinfunction "S_1") (pintype "passive"))
    )
    (net (code "79") (name "V_USB") (class "Default")
      (node (ref "C2") (pin "2") (pinfunction "2_2") (pintype "passive"))
      (node (ref "J2") (pin "1") (pinfunction "VUSB_1") (pintype "passive"))
      (node (ref "R21") (pin "1") (pinfunction "1_1") (pintype "passive"))
      (node (ref "R21") (pin "2") (pinfunction "1_2") (pintype "passive"))
      (node (ref "U2") (pin "7") (pinfunction "VREGIN_7") (pintype "power_in"))
      (node (ref "U2") (pin "8") (pinfunction "VBUS_8") (pintype "power_in"))
    )
    (net (code "80") (name "XTAL1") (class "Default")
      (node (ref "C7") (pin "2") (pinfunction "2_2") (pintype "passive"))
      (node (ref "U1") (pin "34") (pinfunction "XTAL1_34") (pintype "input"))
      (node (ref "Y1") (pin "2") (pinfunction "2_2") (pintype "passive"))
    )
    (net (code "81") (name "XTAL2") (class "Default")
      (node (ref "C10") (pin "2") (pinfunction "2_2") (pintype "passive"))
      (node (ref "U1") (pin "33") (pinfunction "XTAL2_33") (pintype "output"))
      (node (ref "Y1") (pin "1") (pinfunction "1_1") (pintype "passive"))
    )
    (net (code "82") (name "unconnected-(D5-DOUT-Pad2)") (class "Default")
      (node (ref "D5") (pin "2") (pinfunction "DOUT_2") (pintype "output"))
    )
    (net (code "83") (name "unconnected-(J2-ID-Pad4)") (class "Default")
      (node (ref "J2") (pin "4") (pinfunction "ID_4") (pintype "passive"))
    )
    (net (code "84") (name "unconnected-(JP2-Pad7)") (class "Default")
      (node (ref "JP2") (pin "7") (pinfunction "7_7") (pintype "passive"))
    )
    (net (code "85") (name "unconnected-(JP2-Pad13)") (class "Default")
      (node (ref "JP2") (pin "13") (pinfunction "13_13") (pintype "passive"))
    )
    (net (code "86") (name "unconnected-(JP2-Pad15)") (class "Default")
      (node (ref "JP2") (pin "15") (pinfunction "15_15") (pintype "passive"))
    )
    (net (code "87") (name "unconnected-(JP2-Pad16)") (class "Default")
      (node (ref "JP2") (pin "16") (pinfunction "16_16") (pintype "passive"))
    )
    (net (code "88") (name "unconnected-(JP2-Pad17)") (class "Default")
      (node (ref "JP2") (pin "17") (pinfunction "17_17") (pintype "passive"))
    )
    (net (code "89") (name "unconnected-(JP2-Pad19)") (class "Default")
      (node (ref "JP2") (pin "19") (pinfunction "19_19") (pintype "passive"))
    )
    (net (code "90") (name "unconnected-(JP2-Pad21)") (class "Default")
      (node (ref "JP2") (pin "21") (pinfunction "21_21") (pintype "passive"))
    )
    (net (code "91") (name "unconnected-(JP2-Pad22)") (class "Default")
      (node (ref "JP2") (pin "22") (pinfunction "22_22") (pintype "passive"))
    )
    (net (code "92") (name "unconnected-(JP2-Pad26)") (class "Default")
      (node (ref "JP2") (pin "26") (pinfunction "26_26") (pintype "passive"))
    )
    (net (code "93") (name "unconnected-(JP2-Pad27)") (class "Default")
      (node (ref "JP2") (pin "27") (pinfunction "27_27") (pintype "passive"))
    )
    (net (code "94") (name "unconnected-(JP2-Pad28)") (class "Default")
      (node (ref "JP2") (pin "28") (pinfunction "28_28") (pintype "passive"))
    )
    (net (code "95") (name "unconnected-(JP2-Pad29)") (class "Default")
      (node (ref "JP2") (pin "29") (pinfunction "29_29") (pintype "passive"))
    )
    (net (code "96") (name "unconnected-(JP2-Pad31)") (class "Default")
      (node (ref "JP2") (pin "31") (pinfunction "31_31") (pintype "passive"))
    )
    (net (code "97") (name "unconnected-(JP2-Pad32)") (class "Default")
      (node (ref "JP2") (pin "32") (pinfunction "32_32") (pintype "passive"))
    )
    (net (code "98") (name "unconnected-(JP2-Pad33)") (class "Default")
      (node (ref "JP2") (pin "33") (pinfunction "33_33") (pintype "passive"))
    )
    (net (code "99") (name "unconnected-(JP2-Pad35)") (class "Default")
      (node (ref "JP2") (pin "35") (pinfunction "35_35") (pintype "passive"))
    )
    (net (code "100") (name "unconnected-(JP2-Pad36)") (class "Default")
      (node (ref "JP2") (pin "36") (pinfunction "36_36") (pintype "passive"))
    )
    (net (code "101") (name "unconnected-(JP2-Pad37)") (class "Default")
      (node (ref "JP2") (pin "37") (pinfunction "37_37") (pintype "passive"))
    )
    (net (code "102") (name "unconnected-(JP2-Pad38)") (class "Default")
      (node (ref "JP2") (pin "38") (pinfunction "38_38") (pintype "passive"))
    )
    (net (code "103") (name "unconnected-(JP2-Pad40)") (class "Default")
      (node (ref "JP2") (pin "40") (pinfunction "40_40") (pintype "passive"))
    )
    (net (code "104") (name "unconnected-(SW1-Pad2)") (class "Default")
      (node (ref "SW1") (pin "2") (pinfunction "2_2") (pintype "passive"))
    )
    (net (code "105") (name "unconnected-(SW1-Pad4)") (class "Default")
      (node (ref "SW1") (pin "4") (pinfunction "4_4") (pintype "passive"))
    )
    (net (code "106") (name "unconnected-(U1-(CLKO{slash}ICP3{slash}INT7)_PE7-Pad9)") (class "Default")
      (node (ref "U1") (pin "9") (pinfunction "(CLKO/ICP3/INT7)_PE7_9") (pintype "bidirectional"))
    )
    (net (code "107") (name "unconnected-(U1-(ICP1)_PD4-Pad47)") (class "Default")
      (node (ref "U1") (pin "47") (pinfunction "(ICP1)_PD4_47") (pintype "bidirectional"))
    )
    (net (code "108") (name "unconnected-(U1-(ICP4)_PL0-Pad35)") (class "Default")
      (node (ref "U1") (pin "35") (pinfunction "(ICP4)_PL0_35") (pintype "bidirectional"))
    )
    (net (code "109") (name "unconnected-(U1-(ICP5)_PL1-Pad36)") (class "Default")
      (node (ref "U1") (pin "36") (pinfunction "(ICP5)_PL1_36") (pintype "bidirectional"))
    )
    (net (code "110") (name "unconnected-(U1-(OC1B{slash}PCINT6)_PB6-Pad25)") (class "Default")
      (node (ref "U1") (pin "25") (pinfunction "(OC1B/PCINT6)_PB6_25") (pintype "bidirectional"))
    )
    (net (code "111") (name "unconnected-(U1-(OC5A)_PL3-Pad38)") (class "Default")
      (node (ref "U1") (pin "38") (pinfunction "(OC5A)_PL3_38") (pintype "bidirectional"))
    )
    (net (code "112") (name "unconnected-(U1-(OC5B)_PL4-Pad39)") (class "Default")
      (node (ref "U1") (pin "39") (pinfunction "(OC5B)_PL4_39") (pintype "bidirectional"))
    )
    (net (code "113") (name "unconnected-(U1-(RXD1{slash}INT2)_PD2-Pad45)") (class "Default")
      (node (ref "U1") (pin "45") (pinfunction "(RXD1/INT2)_PD2_45") (pintype "bidirectional"))
    )
    (net (code "114") (name "unconnected-(U1-(RXD2)_PH0-Pad12)") (class "Default")
      (node (ref "U1") (pin "12") (pinfunction "(RXD2)_PH0_12") (pintype "bidirectional"))
    )
    (net (code "115") (name "unconnected-(U1-(T0)_PD7-Pad50)") (class "Default")
      (node (ref "U1") (pin "50") (pinfunction "(T0)_PD7_50") (pintype "bidirectional"))
    )
    (net (code "116") (name "unconnected-(U1-(T1)_PD6-Pad49)") (class "Default")
      (node (ref "U1") (pin "49") (pinfunction "(T1)_PD6_49") (pintype "bidirectional"))
    )
    (net (code "117") (name "unconnected-(U1-(T3{slash}INT6)_PE6-Pad8)") (class "Default")
      (node (ref "U1") (pin "8") (pinfunction "(T3/INT6)_PE6_8") (pintype "bidirectional"))
    )
    (net (code "118") (name "unconnected-(U1-(T4)_PH7-Pad27)") (class "Default")
      (node (ref "U1") (pin "27") (pinfunction "(T4)_PH7_27") (pintype "bidirectional"))
    )
    (net (code "119") (name "unconnected-(U1-(T5)_PL2-Pad37)") (class "Default")
      (node (ref "U1") (pin "37") (pinfunction "(T5)_PL2_37") (pintype "bidirectional"))
    )
    (net (code "120") (name "unconnected-(U1-(TOSC1)_PG4-Pad29)") (class "Default")
      (node (ref "U1") (pin "29") (pinfunction "(TOSC1)_PG4_29") (pintype "bidirectional"))
    )
    (net (code "121") (name "unconnected-(U1-(TOSC2)_PG3-Pad28)") (class "Default")
      (node (ref "U1") (pin "28") (pinfunction "(TOSC2)_PG3_28") (pintype "bidirectional"))
    )
    (net (code "122") (name "unconnected-(U1-(TXD1{slash}INT3)_PD3-Pad46)") (class "Default")
      (node (ref "U1") (pin "46") (pinfunction "(TXD1/INT3)_PD3_46") (pintype "bidirectional"))
    )
    (net (code "123") (name "unconnected-(U1-(TXD2)_PH1-Pad13)") (class "Default")
      (node (ref "U1") (pin "13") (pinfunction "(TXD2)_PH1_13") (pintype "bidirectional"))
    )
    (net (code "124") (name "unconnected-(U1-(XCK0{slash}AIN0)_PE2-Pad4)") (class "Default")
      (node (ref "U1") (pin "4") (pinfunction "(XCK0/AIN0)_PE2_4") (pintype "bidirectional"))
    )
    (net (code "125") (name "unconnected-(U1-(XCK1)_PD5-Pad48)") (class "Default")
      (node (ref "U1") (pin "48") (pinfunction "(XCK1)_PD5_48") (pintype "bidirectional"))
    )
    (net (code "126") (name "unconnected-(U1-(XCK2)_PH2-Pad14)") (class "Default")
      (node (ref "U1") (pin "14") (pinfunction "(XCK2)_PH2_14") (pintype "bidirectional"))
    )
    (net (code "127") (name "unconnected-(U1-AREF-Pad98)") (class "Default")
      (node (ref "U1") (pin "98") (pinfunction "AREF_98") (pintype "input"))
    )
    (net (code "128") (name "unconnected-(U1-OC5C)_PL5-Pad40)") (class "Default")
      (node (ref "U1") (pin "40") (pinfunction "OC5C)_PL5_40") (pintype "bidirectional"))
    )
    (net (code "129") (name "unconnected-(U1-PA0_(AD0)-Pad78)") (class "Default")
      (node (ref "U1") (pin "78") (pinfunction "PA0_(AD0)_78") (pintype "bidirectional"))
    )
    (net (code "130") (name "unconnected-(U1-PA3_(AD3)-Pad75)") (class "Default")
      (node (ref "U1") (pin "75") (pinfunction "PA3_(AD3)_75") (pintype "bidirectional"))
    )
    (net (code "131") (name "unconnected-(U1-PA4_(AD4)-Pad74)") (class "Default")
      (node (ref "U1") (pin "74") (pinfunction "PA4_(AD4)_74") (pintype "bidirectional"))
    )
    (net (code "132") (name "unconnected-(U1-PA5_(AD5)-Pad73)") (class "Default")
      (node (ref "U1") (pin "73") (pinfunction "PA5_(AD5)_73") (pintype "bidirectional"))
    )
    (net (code "133") (name "unconnected-(U1-PA6_(AD6)-Pad72)") (class "Default")
      (node (ref "U1") (pin "72") (pinfunction "PA6_(AD6)_72") (pintype "bidirectional"))
    )
    (net (code "134") (name "unconnected-(U1-PA7_(AD7)-Pad71)") (class "Default")
      (node (ref "U1") (pin "71") (pinfunction "PA7_(AD7)_71") (pintype "bidirectional"))
    )
    (net (code "135") (name "unconnected-(U1-PC0_(A8)-Pad53)") (class "Default")
      (node (ref "U1") (pin "53") (pinfunction "PC0_(A8)_53") (pintype "bidirectional"))
    )
    (net (code "136") (name "unconnected-(U1-PC1_(A9)-Pad54)") (class "Default")
      (node (ref "U1") (pin "54") (pinfunction "PC1_(A9)_54") (pintype "bidirectional"))
    )
    (net (code "137") (name "unconnected-(U1-PC2_(A10)-Pad55)") (class "Default")
      (node (ref "U1") (pin "55") (pinfunction "PC2_(A10)_55") (pintype "bidirectional"))
    )
    (net (code "138") (name "unconnected-(U1-PC3_(A11)-Pad56)") (class "Default")
      (node (ref "U1") (pin "56") (pinfunction "PC3_(A11)_56") (pintype "bidirectional"))
    )
    (net (code "139") (name "unconnected-(U1-PC4_(A12)-Pad57)") (class "Default")
      (node (ref "U1") (pin "57") (pinfunction "PC4_(A12)_57") (pintype "bidirectional"))
    )
    (net (code "140") (name "unconnected-(U1-PC5_(A13)-Pad58)") (class "Default")
      (node (ref "U1") (pin "58") (pinfunction "PC5_(A13)_58") (pintype "bidirectional"))
    )
    (net (code "141") (name "unconnected-(U1-PC6_(A14)-Pad59)") (class "Default")
      (node (ref "U1") (pin "59") (pinfunction "PC6_(A14)_59") (pintype "bidirectional"))
    )
    (net (code "142") (name "unconnected-(U1-PC7_(A15)-Pad60)") (class "Default")
      (node (ref "U1") (pin "60") (pinfunction "PC7_(A15)_60") (pintype "bidirectional"))
    )
    (net (code "143") (name "unconnected-(U1-PF4_(ADC4{slash}TCK)-Pad93)") (class "Default")
      (node (ref "U1") (pin "93") (pinfunction "PF4_(ADC4/TCK)_93") (pintype "bidirectional"))
    )
    (net (code "144") (name "unconnected-(U1-PF5_(ADC5{slash}TMS)-Pad92)") (class "Default")
      (node (ref "U1") (pin "92") (pinfunction "PF5_(ADC5/TMS)_92") (pintype "bidirectional"))
    )
    (net (code "145") (name "unconnected-(U1-PF6_(ADC6{slash}TDO)-Pad91)") (class "Default")
      (node (ref "U1") (pin "91") (pinfunction "PF6_(ADC6/TDO)_91") (pintype "bidirectional"))
    )
    (net (code "146") (name "unconnected-(U1-PF7_(ADC7{slash}TDI)-Pad90)") (class "Default")
      (node (ref "U1") (pin "90") (pinfunction "PF7_(ADC7/TDI)_90") (pintype "bidirectional"))
    )
    (net (code "147") (name "unconnected-(U1-PG1_(~{RD})-Pad52)") (class "Default")
      (node (ref "U1") (pin "52") (pinfunction "PG1_(~{RD})_52") (pintype "bidirectional"))
    )
    (net (code "148") (name "unconnected-(U1-PG2_(ALE)-Pad70)") (class "Default")
      (node (ref "U1") (pin "70") (pinfunction "PG2_(ALE)_70") (pintype "bidirectional"))
    )
    (net (code "149") (name "unconnected-(U1-PJ0_(RXD3{slash}PCINT9)-Pad63)") (class "Default")
      (node (ref "U1") (pin "63") (pinfunction "PJ0_(RXD3/PCINT9)_63") (pintype "bidirectional"))
    )
    (net (code "150") (name "unconnected-(U1-PJ1_(TXD3{slash}PCINT10)-Pad64)") (class "Default")
      (node (ref "U1") (pin "64") (pinfunction "PJ1_(TXD3/PCINT10)_64") (pintype "bidirectional"))
    )
    (net (code "151") (name "unconnected-(U1-PJ2_(XCK3{slash}PCINT11)-Pad65)") (class "Default")
      (node (ref "U1") (pin "65") (pinfunction "PJ2_(XCK3/PCINT11)_65") (pintype "bidirectional"))
    )
    (net (code "152") (name "unconnected-(U1-PJ3_(PCINT12)-Pad66)") (class "Default")
      (node (ref "U1") (pin "66") (pinfunction "PJ3_(PCINT12)_66") (pintype "bidirectional"))
    )
    (net (code "153") (name "unconnected-(U1-PJ4_(PCINT13)-Pad67)") (class "Default")
      (node (ref "U1") (pin "67") (pinfunction "PJ4_(PCINT13)_67") (pintype "bidirectional"))
    )
    (net (code "154") (name "unconnected-(U1-PJ5_(PCINT14)-Pad68)") (class "Default")
      (node (ref "U1") (pin "68") (pinfunction "PJ5_(PCINT14)_68") (pintype "bidirectional"))
    )
    (net (code "155") (name "unconnected-(U1-PJ6_(PCINT15)-Pad69)") (class "Default")
      (node (ref "U1") (pin "69") (pinfunction "PJ6_(PCINT15)_69") (pintype "bidirectional"))
    )
    (net (code "156") (name "unconnected-(U1-PJ7-Pad79)") (class "Default")
      (node (ref "U1") (pin "79") (pinfunction "PJ7_79") (pintype "bidirectional"))
    )
    (net (code "157") (name "unconnected-(U1-PK0_(ADC8{slash}PCINT16)-Pad89)") (class "Default")
      (node (ref "U1") (pin "89") (pinfunction "PK0_(ADC8/PCINT16)_89") (pintype "bidirectional"))
    )
    (net (code "158") (name "unconnected-(U1-PK1_(ADC9{slash}PCINT17)-Pad88)") (class "Default")
      (node (ref "U1") (pin "88") (pinfunction "PK1_(ADC9/PCINT17)_88") (pintype "bidirectional"))
    )
    (net (code "159") (name "unconnected-(U1-PK2_(ADC10{slash}PCINT18)-Pad87)") (class "Default")
      (node (ref "U1") (pin "87") (pinfunction "PK2_(ADC10/PCINT18)_87") (pintype "bidirectional"))
    )
    (net (code "160") (name "unconnected-(U1-PK3_(ADC11{slash}PCINT19)-Pad86)") (class "Default")
      (node (ref "U1") (pin "86") (pinfunction "PK3_(ADC11/PCINT19)_86") (pintype "bidirectional"))
    )
    (net (code "161") (name "unconnected-(U1-PK4_(ADC12{slash}PCINT20)-Pad85)") (class "Default")
      (node (ref "U1") (pin "85") (pinfunction "PK4_(ADC12/PCINT20)_85") (pintype "bidirectional"))
    )
    (net (code "162") (name "unconnected-(U1-PK5_(ADC13{slash}PCINT21)-Pad84)") (class "Default")
      (node (ref "U1") (pin "84") (pinfunction "PK5_(ADC13/PCINT21)_84") (pintype "bidirectional"))
    )
    (net (code "163") (name "unconnected-(U1-PK6_(ADC14{slash}PCINT22)-Pad83)") (class "Default")
      (node (ref "U1") (pin "83") (pinfunction "PK6_(ADC14/PCINT22)_83") (pintype "bidirectional"))
    )
    (net (code "164") (name "unconnected-(U1-PK7_(ADC15{slash}PCINT23)-Pad82)") (class "Default")
      (node (ref "U1") (pin "82") (pinfunction "PK7_(ADC15/PCINT23)_82") (pintype "bidirectional"))
    )
    (net (code "165") (name "unconnected-(U1-PL6-Pad41)") (class "Default")
      (node (ref "U1") (pin "41") (pinfunction "PL6_41") (pintype "bidirectional"))
    )
    (net (code "166") (name "unconnected-(U1-PL7-Pad42)") (class "Default")
      (node (ref "U1") (pin "42") (pinfunction "PL7_42") (pintype "bidirectional"))
    )
    (net (code "167") (name "unconnected-(U2-CHR0-Pad15)") (class "Default")
      (node (ref "U2") (pin "15") (pinfunction "CHR0_15") (pintype "output"))
    )
    (net (code "168") (name "unconnected-(U2-CHR1-Pad14)") (class "Default")
      (node (ref "U2") (pin "14") (pinfunction "CHR1_14") (pintype "output"))
    )
    (net (code "169") (name "unconnected-(U2-CHREN-Pad13)") (class "Default")
      (node (ref "U2") (pin "13") (pinfunction "CHREN_13") (pintype "output"))
    )
    (net (code "170") (name "unconnected-(U2-CTS-Pad23)") (class "Default")
      (node (ref "U2") (pin "23") (pinfunction "CTS_23") (pintype "input"))
    )
    (net (code "171") (name "unconnected-(U2-DCD-Pad1)") (class "Default")
      (node (ref "U2") (pin "1") (pinfunction "DCD_1") (pintype "input"))
    )
    (net (code "172") (name "unconnected-(U2-DSR-Pad27)") (class "Default")
      (node (ref "U2") (pin "27") (pinfunction "DSR_27") (pintype "input"))
    )
    (net (code "173") (name "unconnected-(U2-GPIO.2{slash}RS485-Pad17)") (class "Default")
      (node (ref "U2") (pin "17") (pinfunction "GPIO.2/RS485_17") (pintype "bidirectional"))
    )
    (net (code "174") (name "unconnected-(U2-GPIO.3{slash}WAKEUP-Pad16)") (class "Default")
      (node (ref "U2") (pin "16") (pinfunction "GPIO.3/WAKEUP_16") (pintype "bidirectional"))
    )
    (net (code "175") (name "unconnected-(U2-GPIO.4-Pad22)") (class "Default")
      (node (ref "U2") (pin "22") (pinfunction "GPIO.4_22") (pintype "bidirectional"))
    )
    (net (code "176") (name "unconnected-(U2-GPIO.5-Pad21)") (class "Default")
      (node (ref "U2") (pin "21") (pinfunction "GPIO.5_21") (pintype "bidirectional"))
    )
    (net (code "177") (name "unconnected-(U2-GPIO.6-Pad20)") (class "Default")
      (node (ref "U2") (pin "20") (pinfunction "GPIO.6_20") (pintype "bidirectional"))
    )
    (net (code "178") (name "unconnected-(U2-RI{slash}CLK-Pad2)") (class "Default")
      (node (ref "U2") (pin "2") (pinfunction "RI/CLK_2") (pintype "bidirectional"))
    )
    (net (code "179") (name "unconnected-(U2-RTS-Pad24)") (class "Default")
      (node (ref "U2") (pin "24") (pinfunction "RTS_24") (pintype "output"))
    )
    (net (code "180") (name "unconnected-(U2-SUSPEND-Pad12)") (class "Default")
      (node (ref "U2") (pin "12") (pinfunction "SUSPEND_12") (pintype "output"))
    )
    (net (code "181") (name "unconnected-(U2-~{SUSPENDB}-Pad11)") (class "Default")
      (node (ref "U2") (pin "11") (pinfunction "~{SUSPENDB}_11") (pintype "output"))
    )
    (net (code "182") (name "unconnected-(U4-PG-PadP$7)") (class "Default")
      (node (ref "U4") (pin "P$7") (pinfunction "PG_P$7") (pintype "bidirectional"))
    )
    (net (code "183") (name "unconnected-(U5-NC-1-Pad3)") (class "Default")
      (node (ref "U5") (pin "3") (pinfunction "NC-1_3") (pintype "bidirectional"))
    )
    (net (code "184") (name "unconnected-(U5-NC-Pad5)") (class "Default")
      (node (ref "U5") (pin "5") (pinfunction "NC_5") (pintype "bidirectional"))
    )
    (net (code "185") (name "unconnected-(U6-ST-Pad9)") (class "Default")
      (node (ref "U6") (pin "9") (pinfunction "ST_9") (pintype "output"))
    )
    (net (code "186") (name "unconnected-(U8-VREF-Pad5)") (class "Default")
      (node (ref "U8") (pin "5") (pinfunction "VREF_5") (pintype "passive"))
    )
    (net (code "187") (name "unconnected-(U9-CLKOUT{slash}SOF-Pad3)") (class "Default")
      (node (ref "U9") (pin "3") (pinfunction "CLKOUT/SOF_3") (pintype "output"))
    )
    (net (code "188") (name "unconnected-(U9-~{INT}-Pad12)") (class "Default")
      (node (ref "U9") (pin "12") (pinfunction "~{INT}_12") (pintype "output"))
    )
    (net (code "189") (name "unconnected-(U9-~{RX0BF}-Pad11)") (class "Default")
      (node (ref "U9") (pin "11") (pinfunction "~{RX0BF}_11") (pintype "output"))
    )
    (net (code "190") (name "unconnected-(U9-~{RX1BF}-Pad10)") (class "Default")
      (node (ref "U9") (pin "10") (pinfunction "~{RX1BF}_10") (pintype "output"))
    )
    (net (code "191") (name "unconnected-(U9-~{TX0RTS}-Pad4)") (class "Default")
      (node (ref "U9") (pin "4") (pinfunction "~{TX0RTS}_4") (pintype "input"))
    )
    (net (code "192") (name "unconnected-(U9-~{TX1RTS}-Pad5)") (class "Default")
      (node (ref "U9") (pin "5") (pinfunction "~{TX1RTS}_5") (pintype "input"))
    )
    (net (code "193") (name "unconnected-(U9-~{TX2RTS}-Pad6)") (class "Default")
      (node (ref "U9") (pin "6") (pinfunction "~{TX2RTS}_6") (pintype "input"))
    )
    (net (code "194") (name "~{PG}") (class "Default")
      (node (ref "Q1") (pin "1") (pinfunction "G_1") (pintype "bidirectional"))
      (node (ref "Q2") (pin "3") (pinfunction "D_3") (pintype "bidirectional"))
    )
  )
)
